# ESP-HI-C3-RevA-schematic.net
KiCad netlist of a schematic drawn in EasyEDA
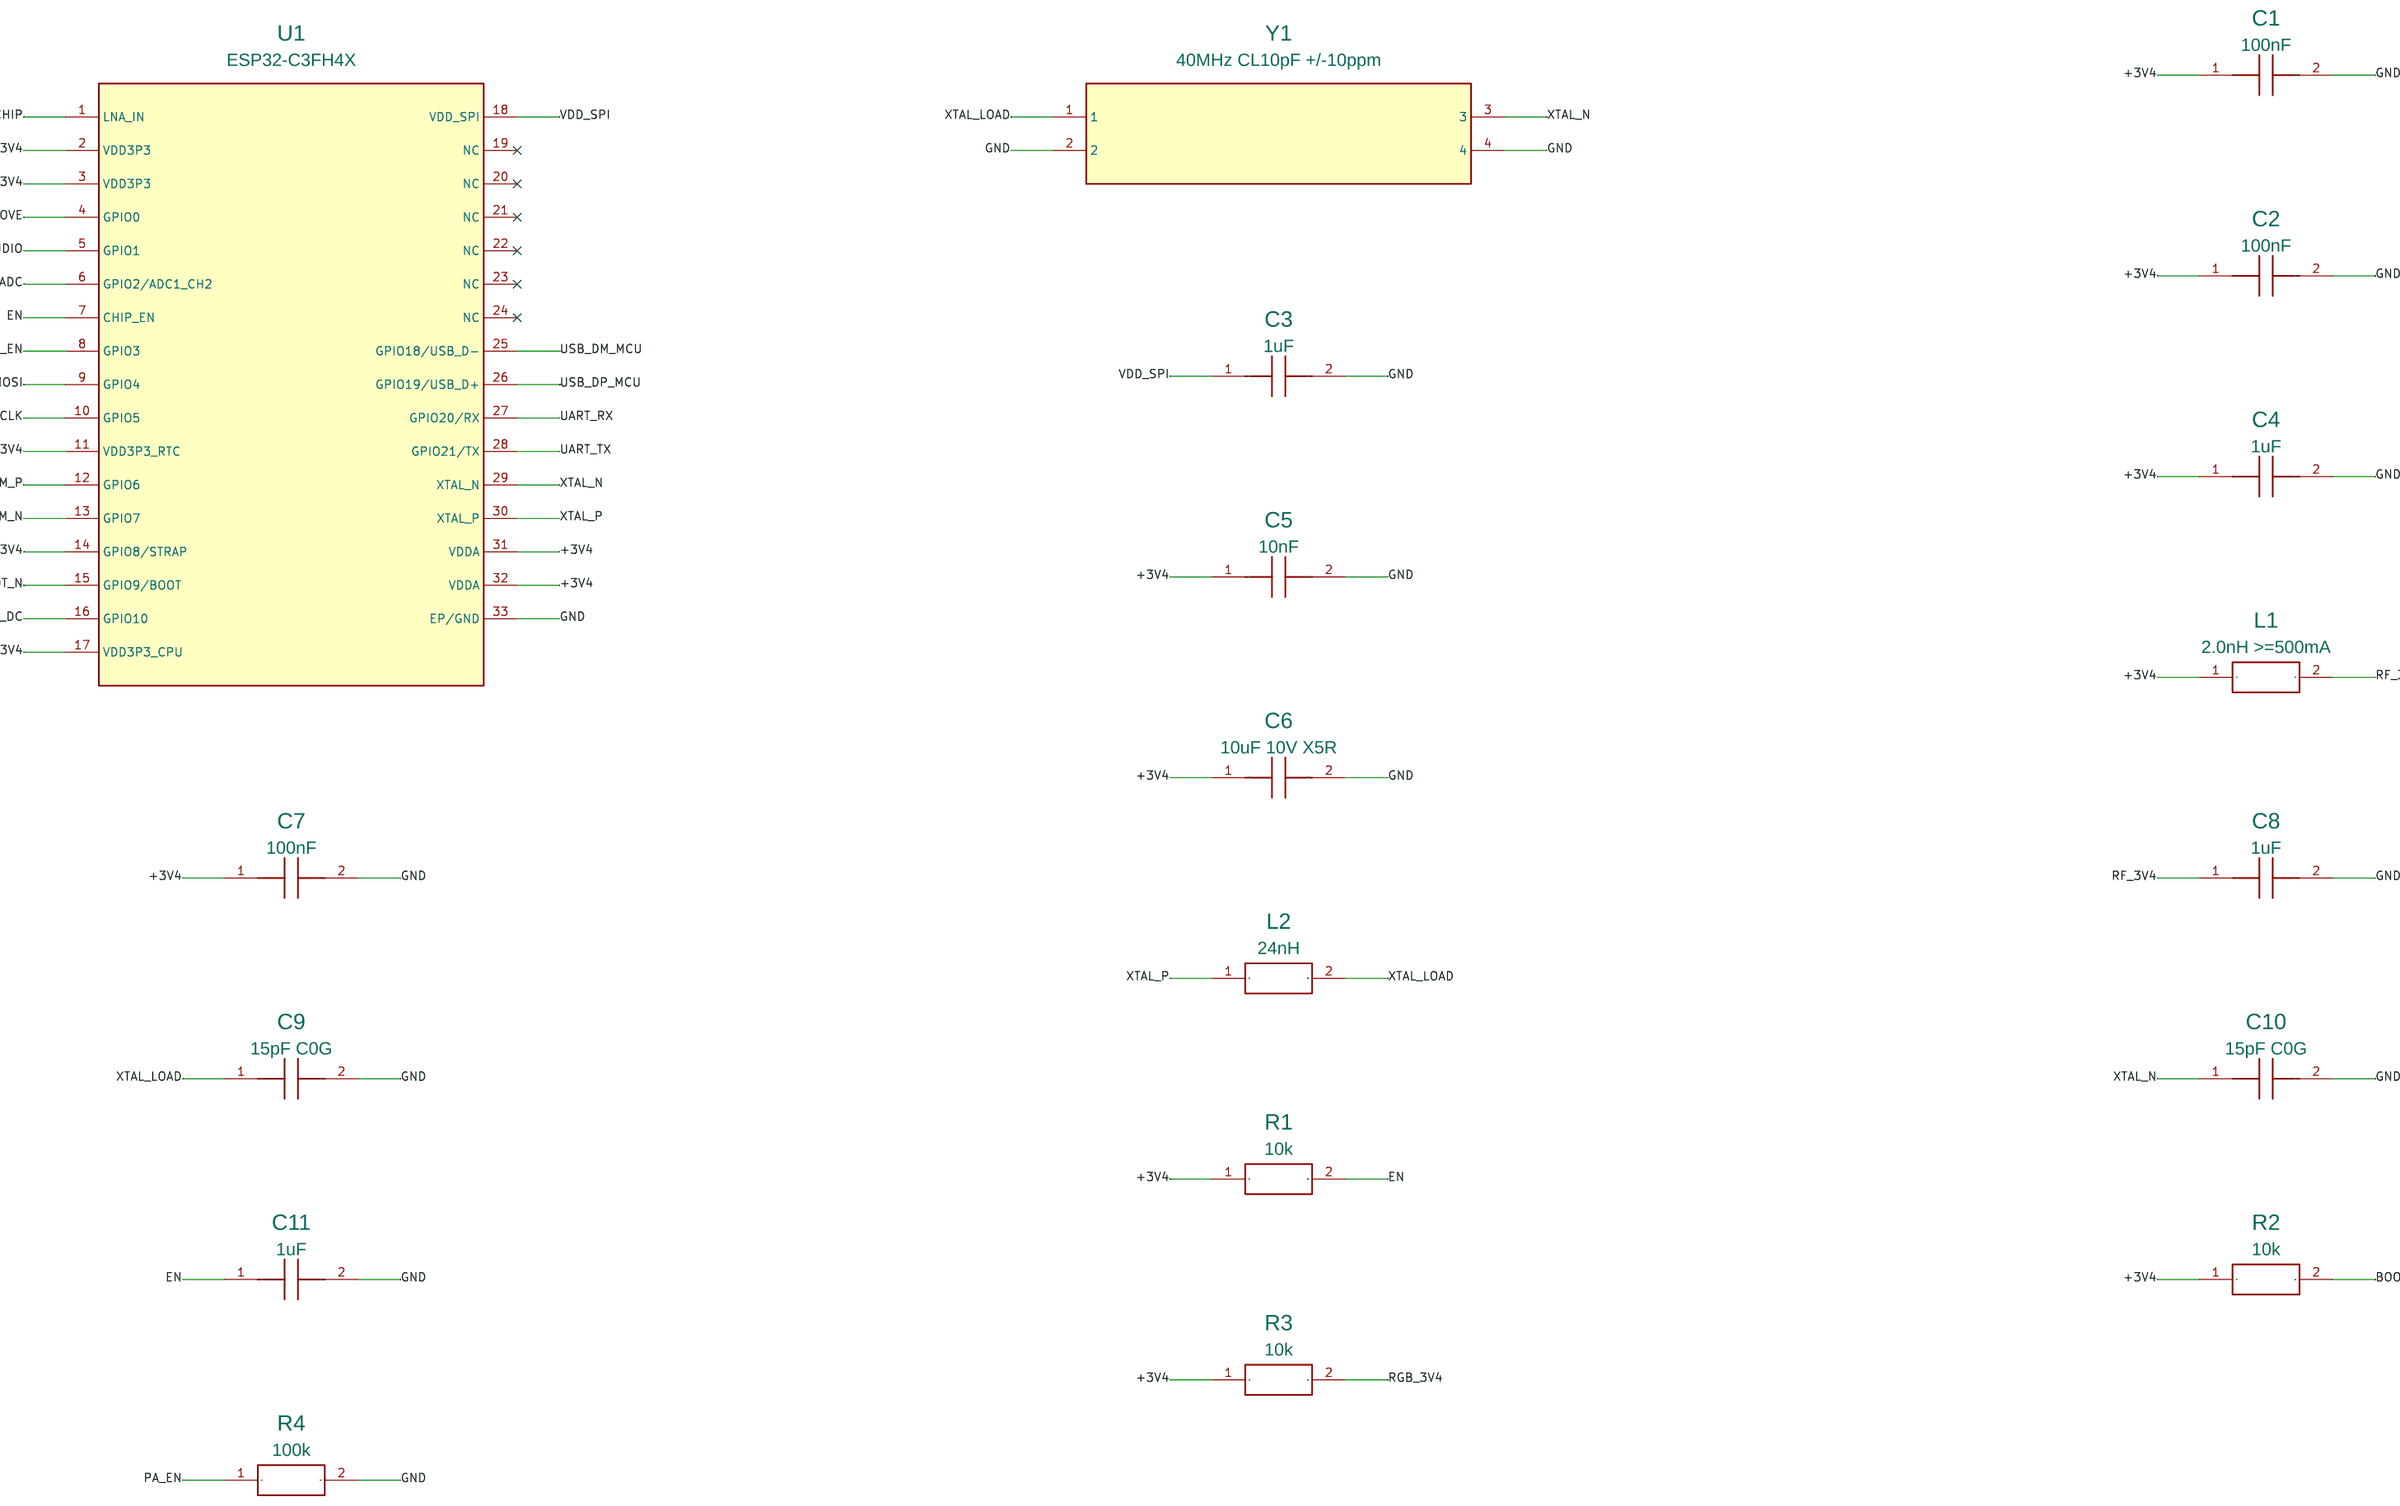
[diagram p0: 01 MCU, crystal and reset]
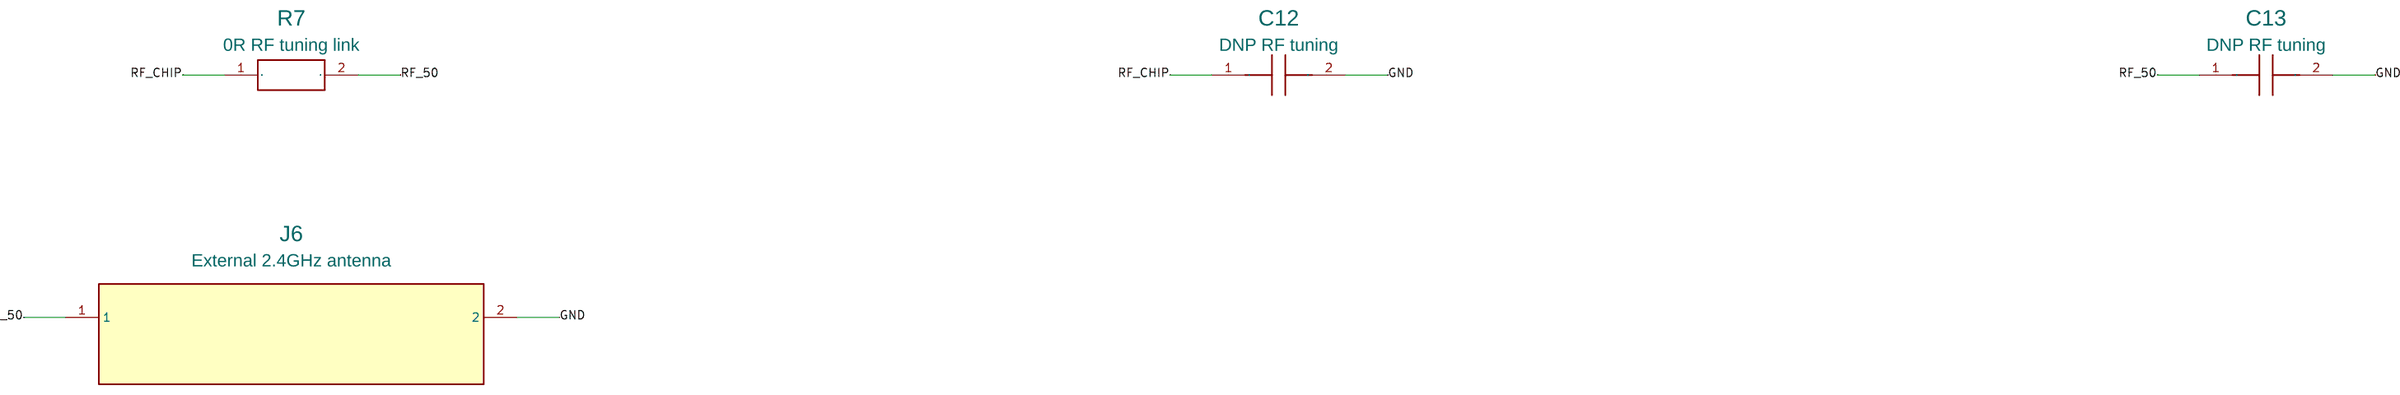
[diagram p1: 02 External antenna and matching]
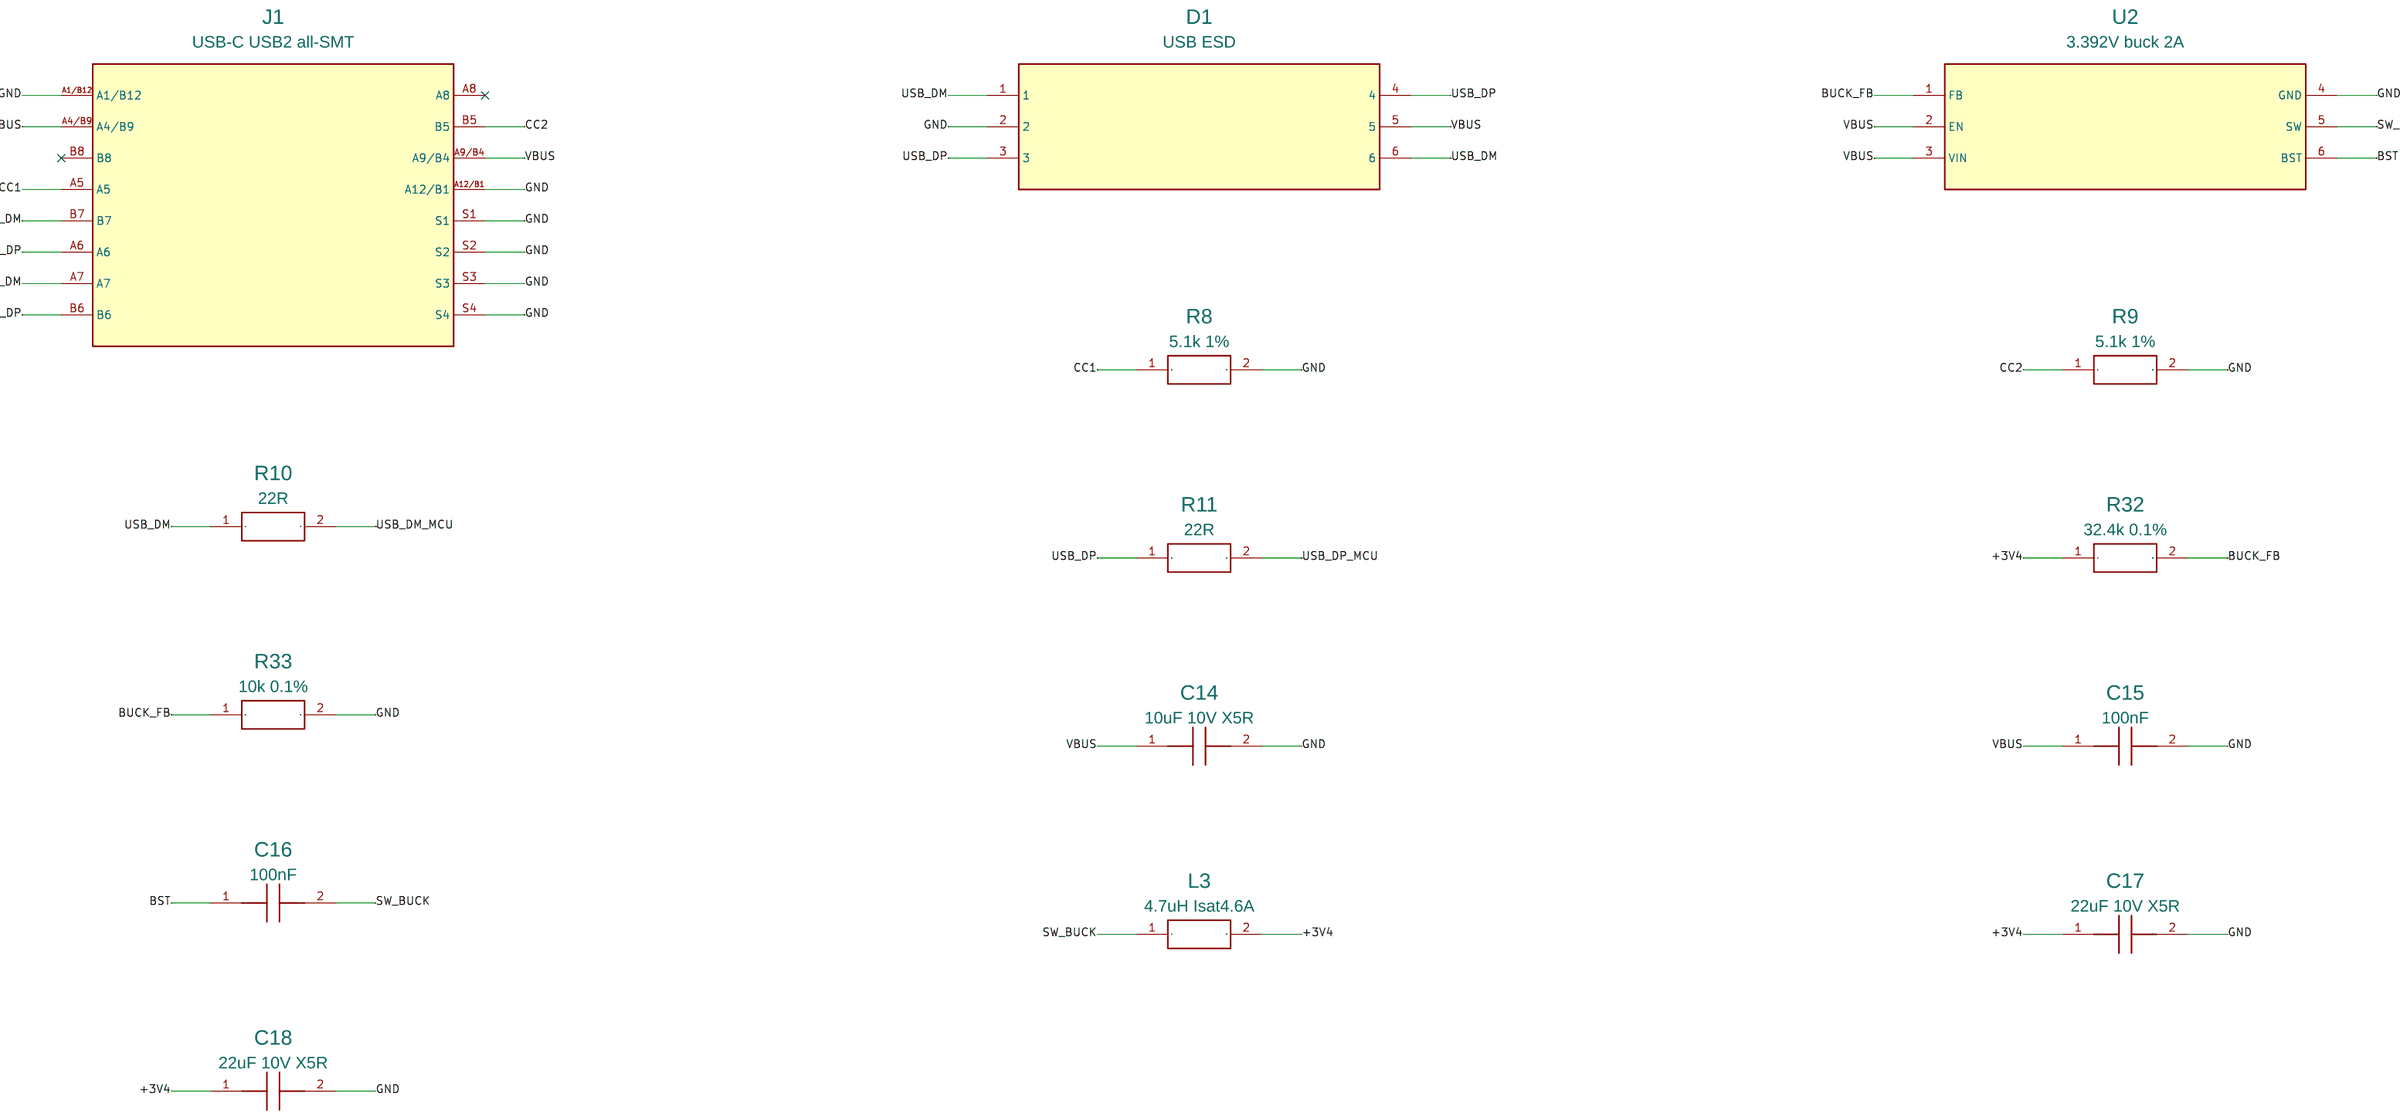
[diagram p2: 03 USB-C and regulated supply]
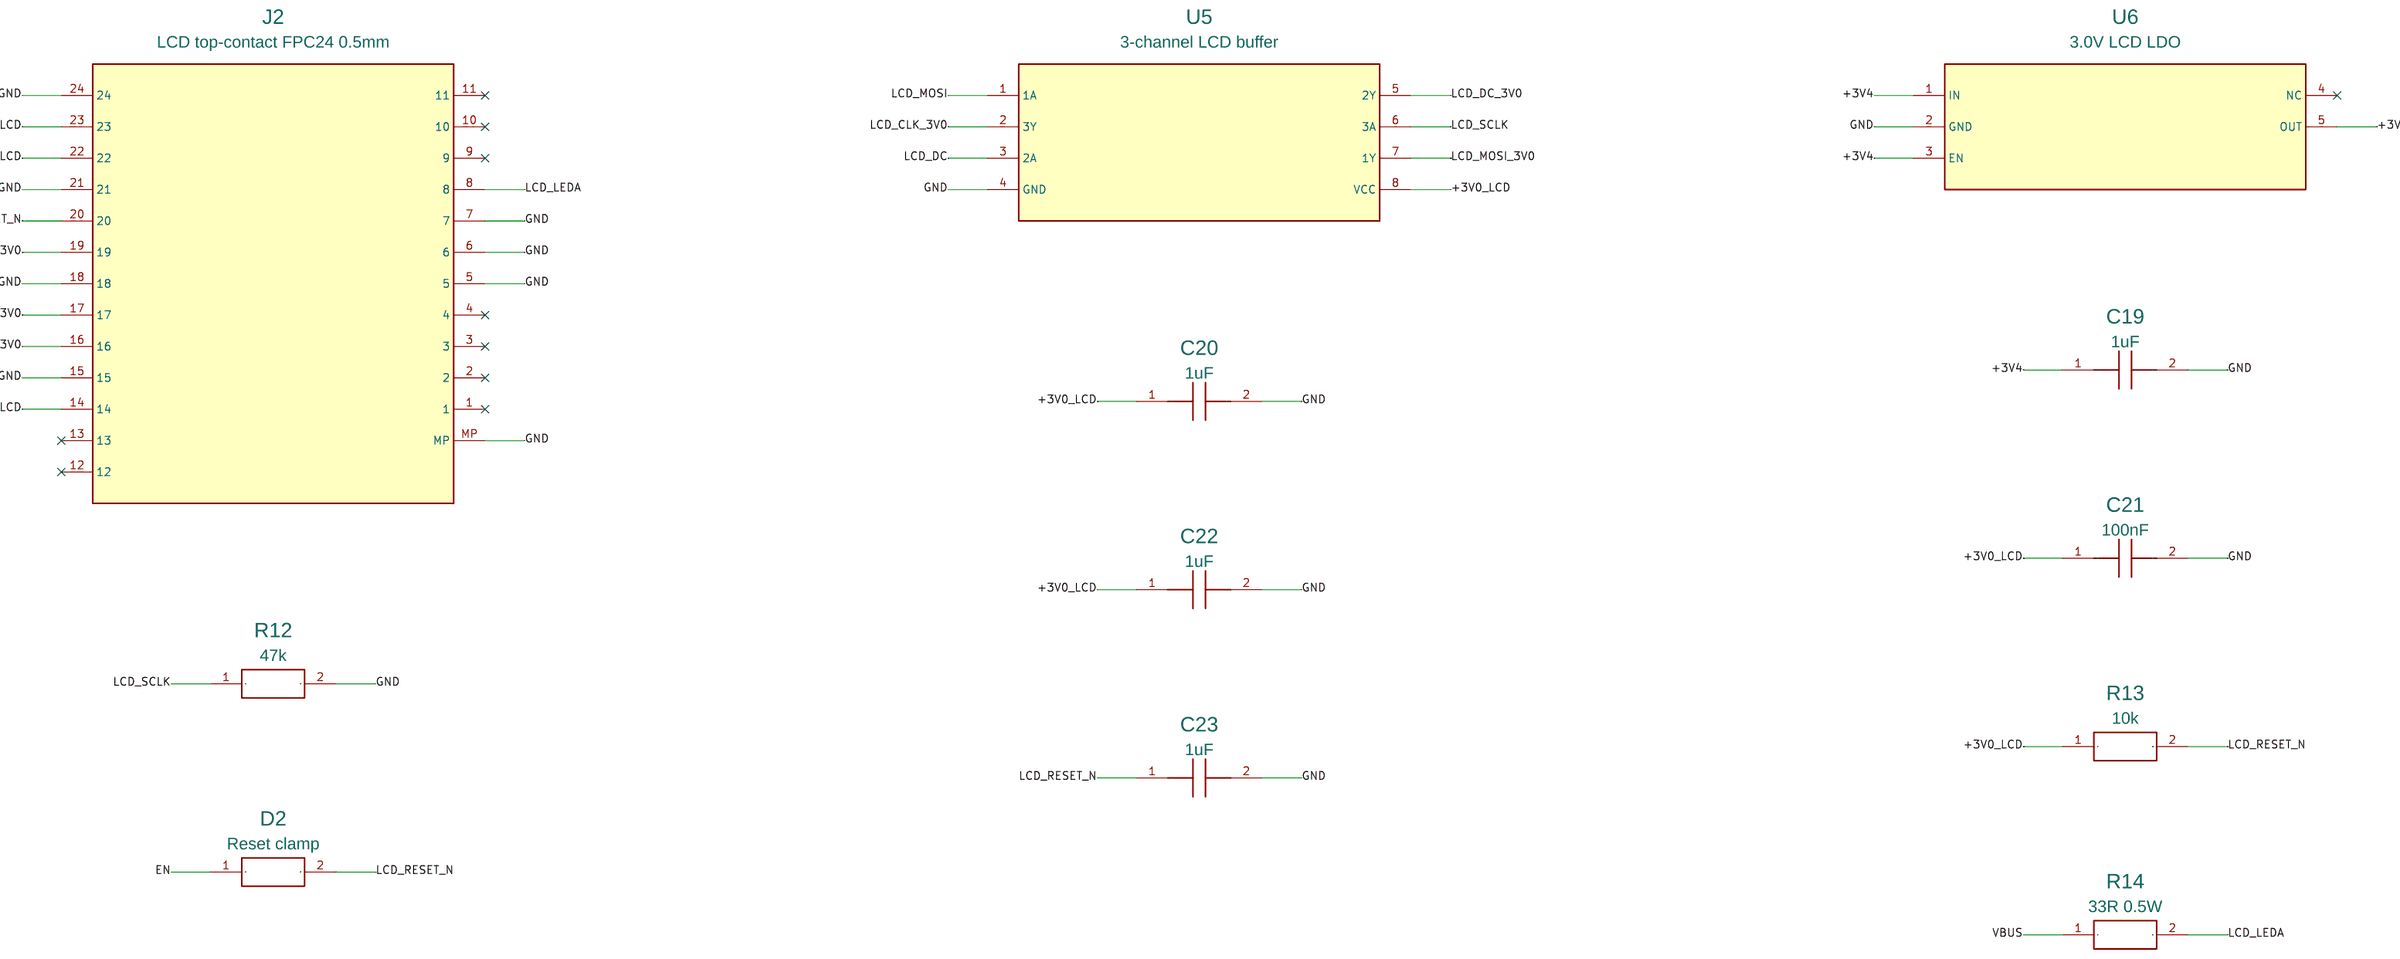
[diagram p3: 04 128x160 SPI display]
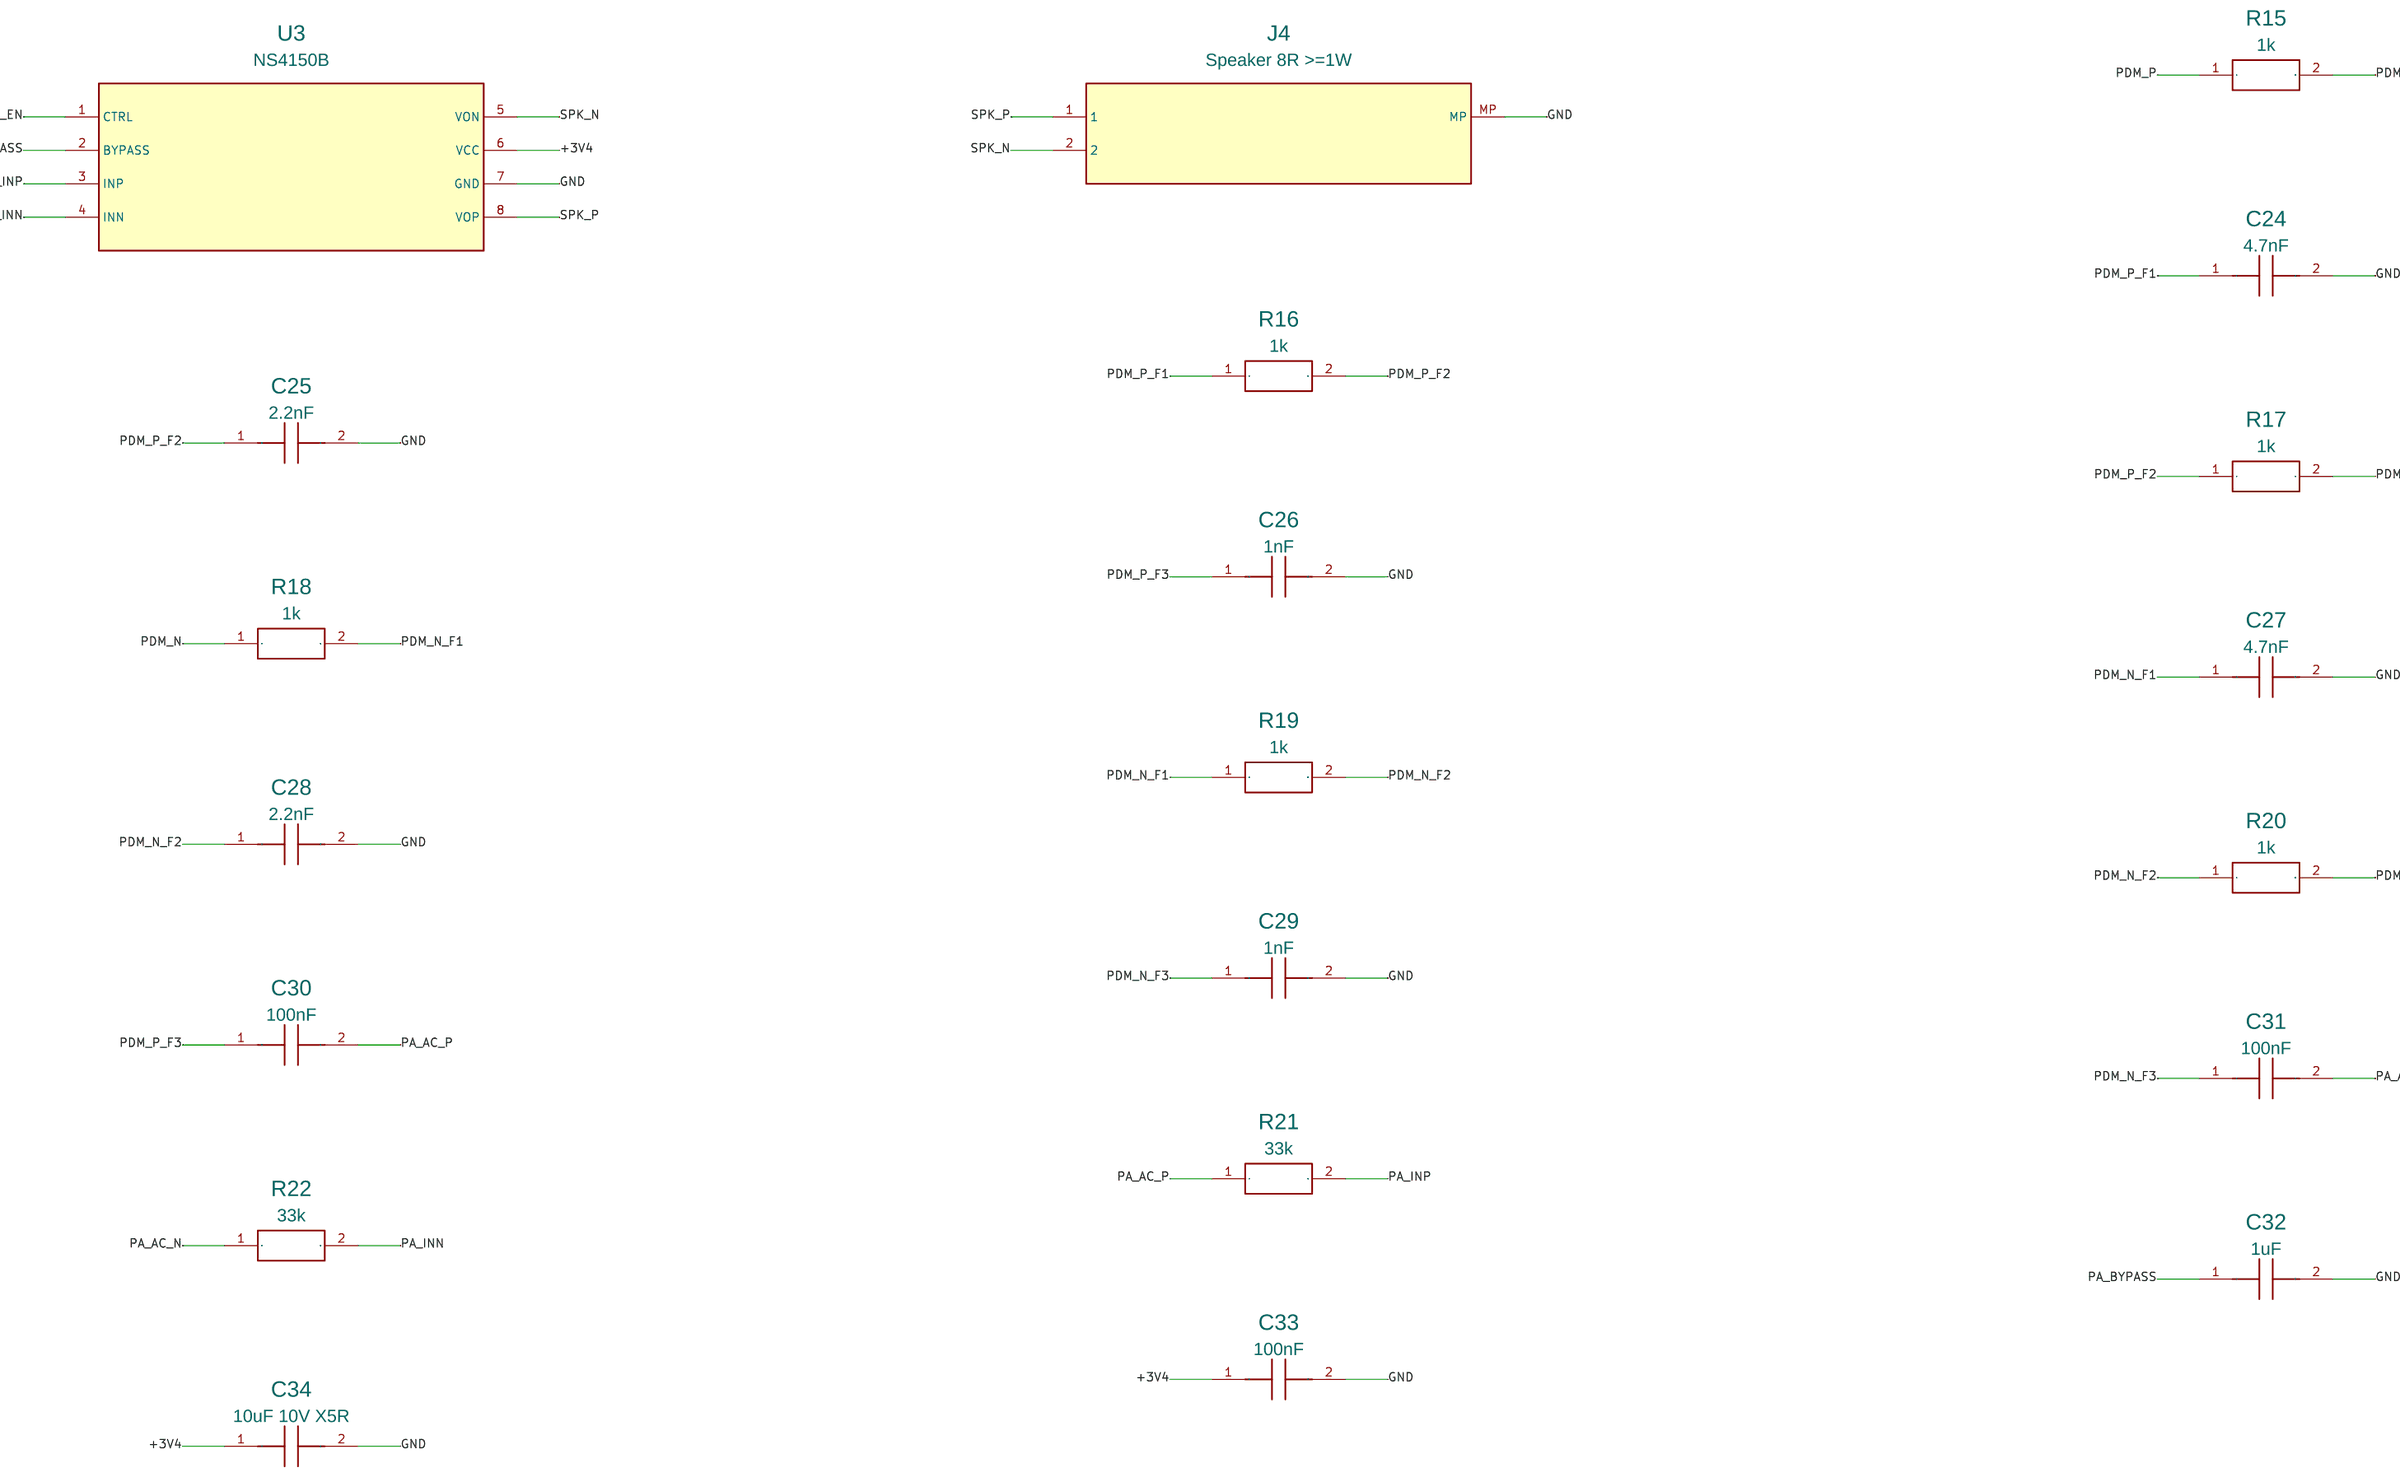
[diagram p4: 05 PDM reconstruction and speaker]
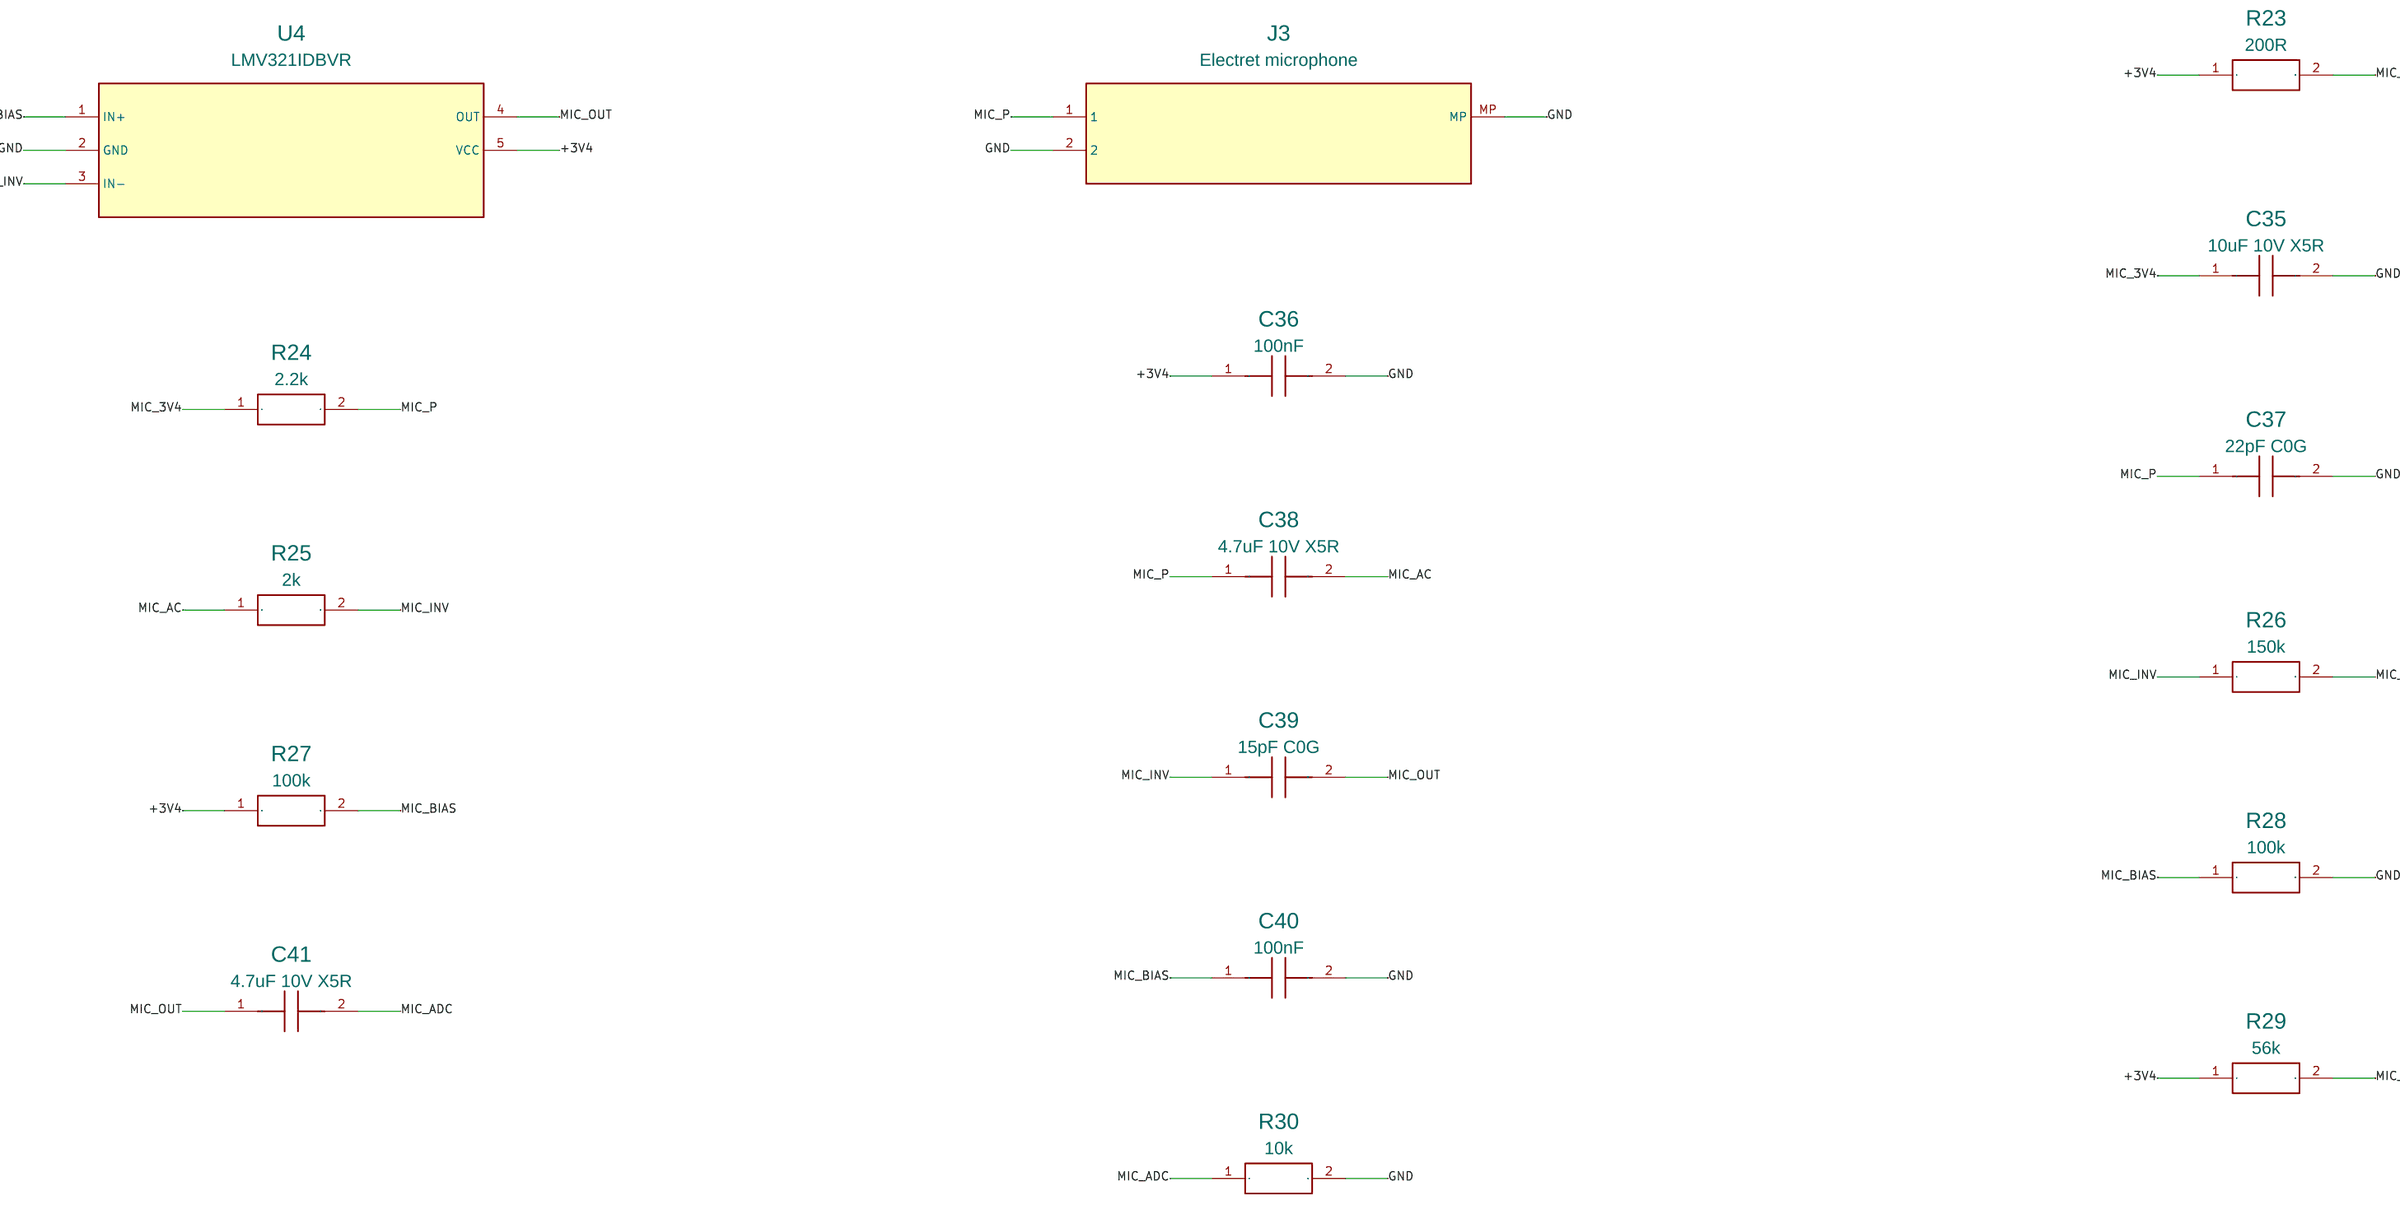
[diagram p5: 06 Electret microphone and ADC]
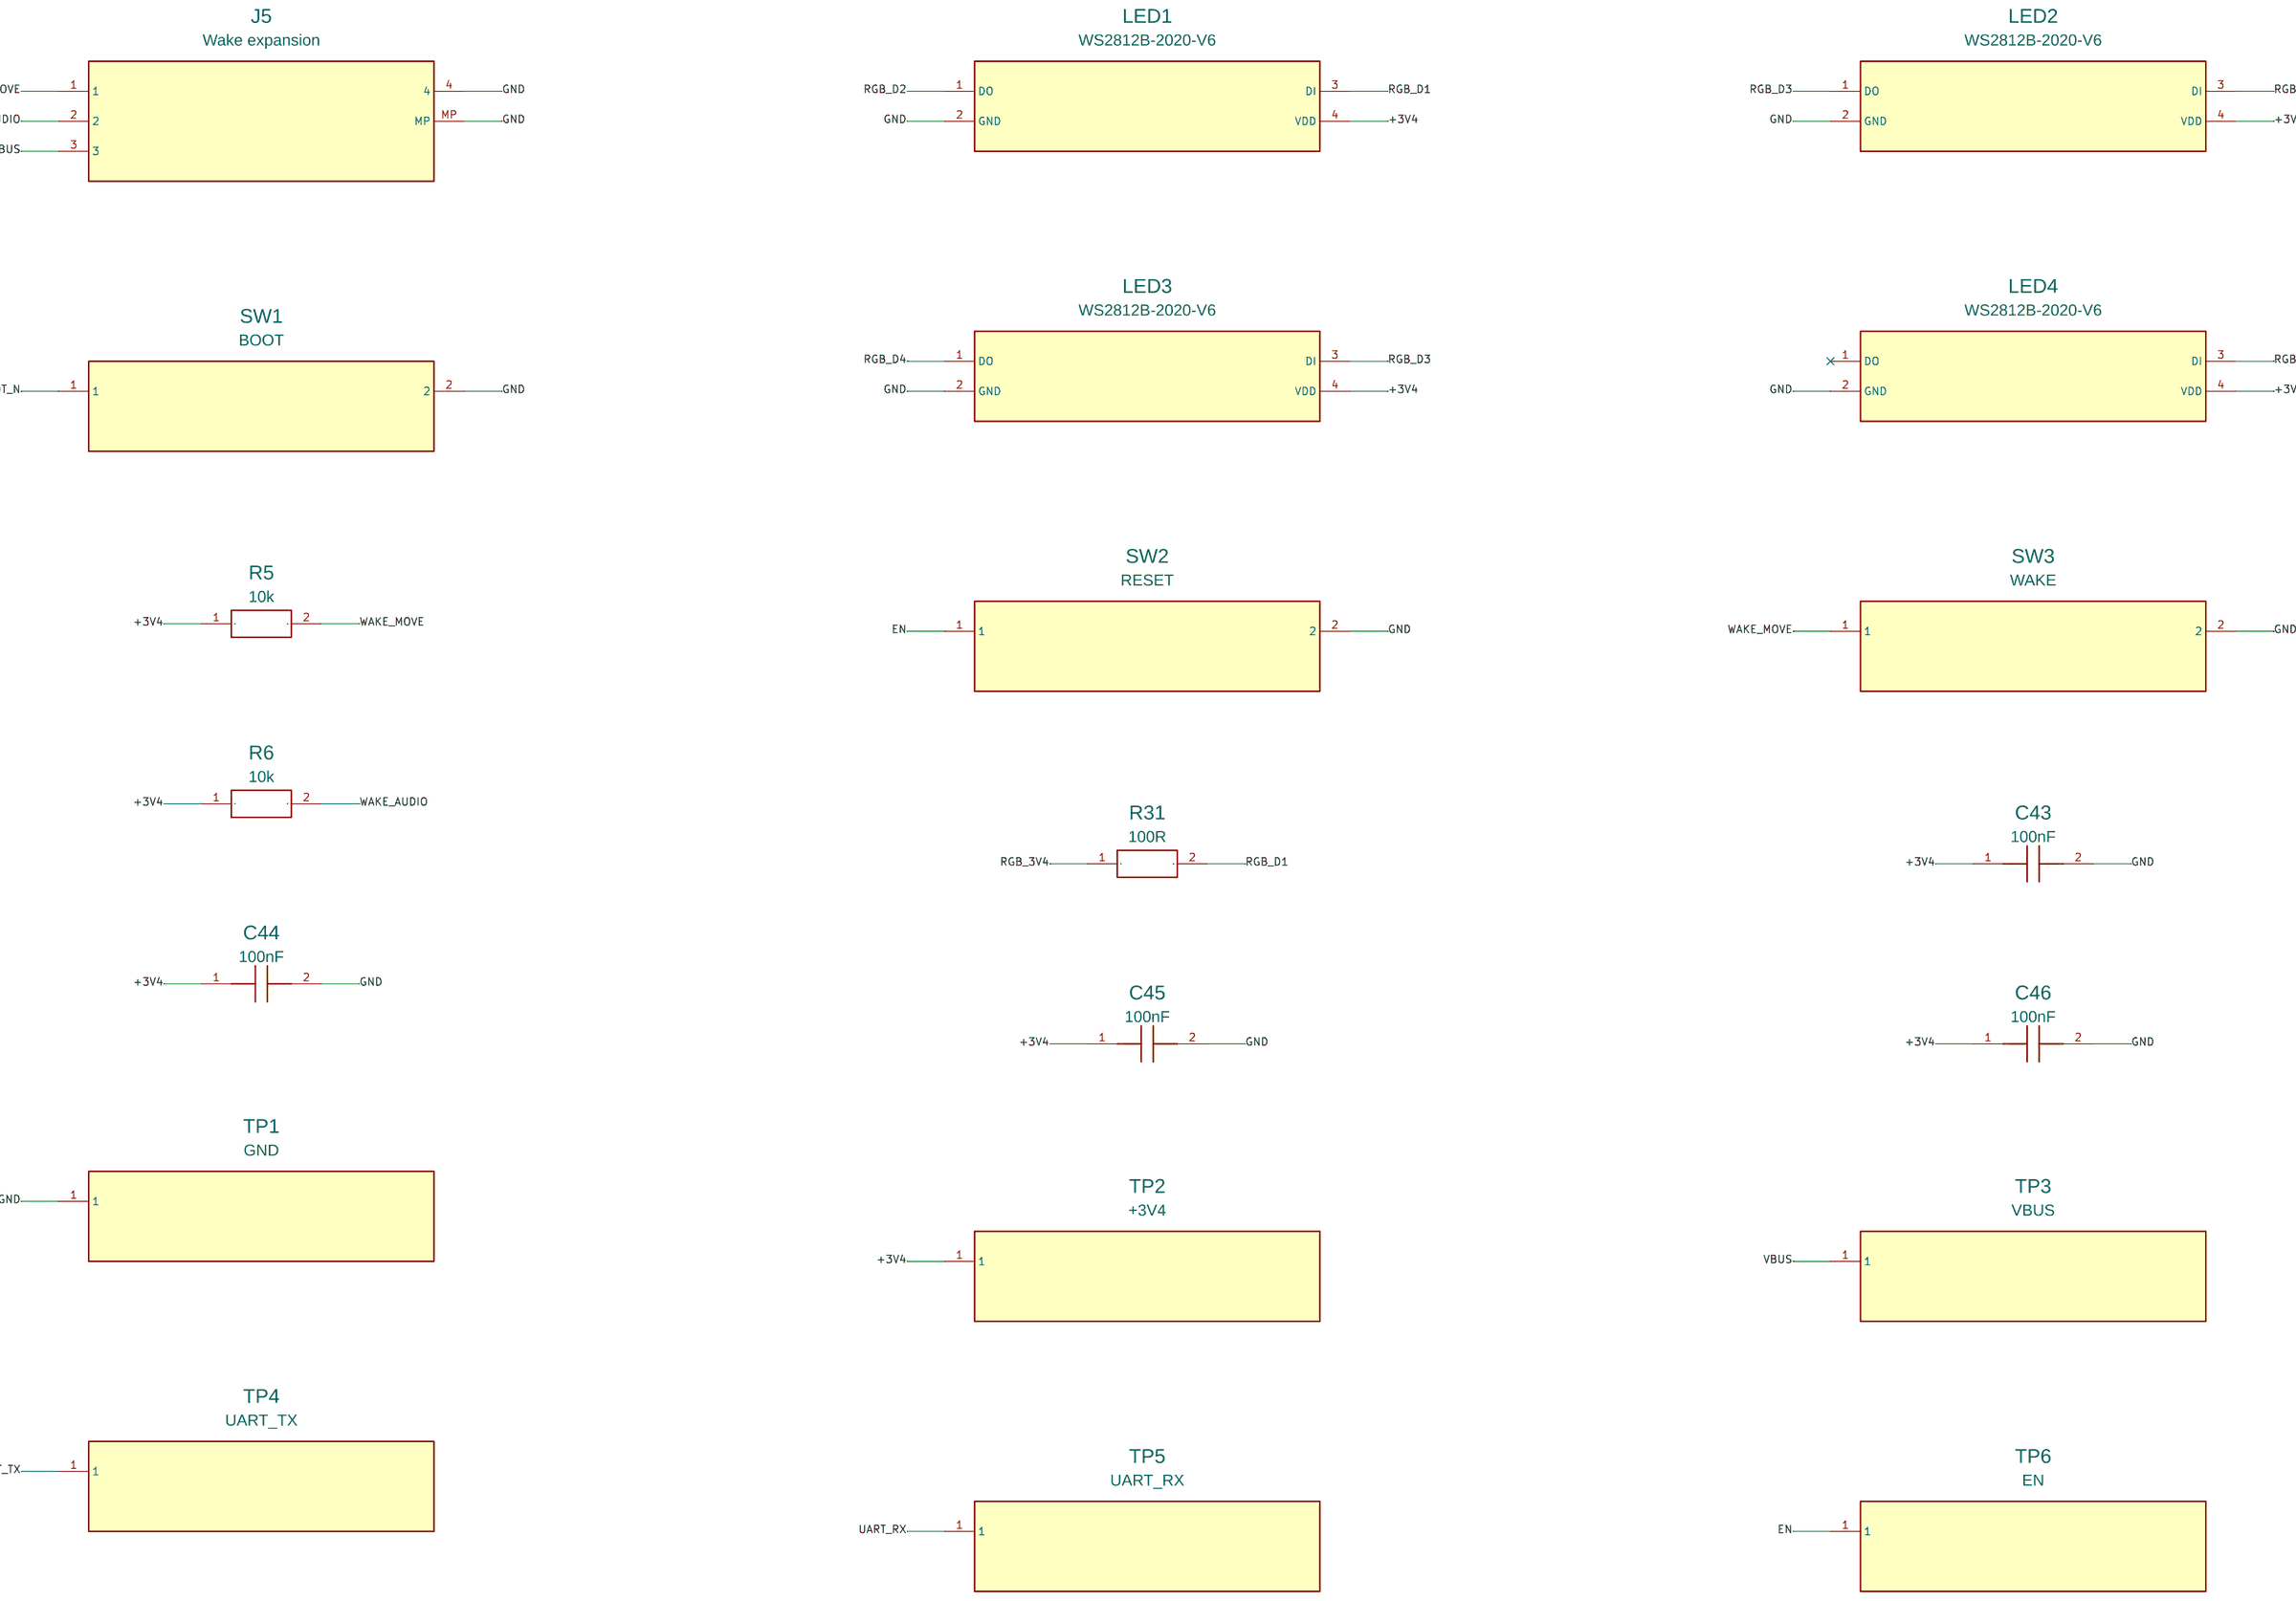
[diagram p6: 07 Buttons, RGB and external IO]

(export (version "E")
  (design (tool "Eeschema 10.0.6"))
  (components
    (comp (ref "C1") (value "100nF") (libsource (lib "") (part "Unknown_1490_145")))
    (comp (ref "C2") (value "100nF") (libsource (lib "") (part "Unknown_1490_265")))
    (comp (ref "C3") (value "1uF") (libsource (lib "") (part "Unknown_900_325")))
    (comp (ref "C4") (value "1uF") (libsource (lib "") (part "Unknown_1490_385")))
    (comp (ref "C5") (value "10nF") (libsource (lib "") (part "Unknown_900_445")))
    (comp (ref "C6") (value "10uF 10V X5R") (libsource (lib "") (part "Unknown_900_565")))
    (comp (ref "C7") (value "100nF") (libsource (lib "") (part "Unknown_310_625")))
    (comp (ref "C8") (value "1uF") (libsource (lib "") (part "Unknown_1490_625")))
    (comp (ref "C9") (value "15pF C0G") (libsource (lib "") (part "Unknown_310_745")))
    (comp (ref "C10") (value "15pF C0G") (libsource (lib "") (part "Unknown_1490_745")))
    (comp (ref "C11") (value "1uF") (libsource (lib "") (part "Unknown_310_865")))
    (comp (ref "L1") (value "2.0nH >=500mA") (libsource (lib "") (part "Unknown_1490_505")))
    (comp (ref "L2") (value "24nH") (libsource (lib "") (part "Unknown_900_685")))
    (comp (ref "R1") (value "10k") (libsource (lib "") (part "Unknown_900_805")))
    (comp (ref "R2") (value "10k") (libsource (lib "") (part "Unknown_1490_865")))
    (comp (ref "R3") (value "10k") (libsource (lib "") (part "Unknown_900_925")))
    (comp (ref "R4") (value "100k") (libsource (lib "") (part "Unknown_310_985")))
    (comp (ref "U1") (value "ESP32-C3FH4X") (libsource (lib "") (part "Unknown_310_330")))
    (comp (ref "Y1")
      (value "40MHz CL10pF +/-10ppm")
      (fields (field (name "Manufacturer Part") "FA-20H 40.0000MF10Z-K3"))
      (libsource (lib "") (part "Unknown_900_180"))
    )
    (comp (ref "C12") (value "DNP RF tuning") (libsource (lib "") (part "Unknown_900_145")))
    (comp (ref "C13") (value "DNP RF tuning") (libsource (lib "") (part "Unknown_1490_145")))
    (comp (ref "J6")
      (value "External 2.4GHz antenna")
      (fields (field (name "Manufacturer Part") "U.FL-R-SMT-1(10)"))
      (libsource (lib "") (part "Unknown_310_300"))
    )
    (comp (ref "R7") (value "0R RF tuning link") (libsource (lib "") (part "Unknown_310_145")))
    (comp (ref "C14") (value "10uF 10V X5R") (libsource (lib "") (part "Unknown_900_585")))
    (comp (ref "C15") (value "100nF") (libsource (lib "") (part "Unknown_1490_585")))
    (comp (ref "C16") (value "100nF") (libsource (lib "") (part "Unknown_310_685")))
    (comp (ref "C17") (value "22uF 10V X5R") (libsource (lib "") (part "Unknown_1490_705")))
    (comp (ref "C18") (value "22uF 10V X5R") (libsource (lib "") (part "Unknown_310_805")))
    (comp (ref "D1")
      (value "USB ESD")
      (fields (field (name "Manufacturer Part") "USBLC6-2SC6"))
      (libsource (lib "") (part "Unknown_900_190"))
    )
    (comp (ref "J1")
      (value "USB-C USB2 all-SMT")
      (fields (field (name "Manufacturer Part") "USB4110-GF-A"))
      (libsource (lib "") (part "Unknown_310_240"))
    )
    (comp (ref "L3")
      (value "4.7uH Isat4.6A")
      (fields (field (name "Manufacturer Part") "XAL4030-472MEC"))
      (libsource (lib "") (part "Unknown_900_705"))
    )
    (comp (ref "R8") (value "5.1k 1%") (libsource (lib "") (part "Unknown_900_345")))
    (comp (ref "R9") (value "5.1k 1%") (libsource (lib "") (part "Unknown_1490_345")))
    (comp (ref "R10") (value "22R") (libsource (lib "") (part "Unknown_310_445")))
    (comp (ref "R11") (value "22R") (libsource (lib "") (part "Unknown_900_465")))
    (comp (ref "R32") (value "32.4k 0.1%") (libsource (lib "") (part "Unknown_1490_465")))
    (comp (ref "R33") (value "10k 0.1%") (libsource (lib "") (part "Unknown_310_565")))
    (comp (ref "U2")
      (value "3.392V buck 2A")
      (fields (field (name "Manufacturer Part") "AP63200WU-7"))
      (libsource (lib "") (part "Unknown_1490_190"))
    )
    (comp (ref "C19") (value "1uF") (libsource (lib "") (part "Unknown_1490_345")))
    (comp (ref "C20") (value "1uF") (libsource (lib "") (part "Unknown_900_365")))
    (comp (ref "C21") (value "100nF") (libsource (lib "") (part "Unknown_1490_465")))
    (comp (ref "C22") (value "1uF") (libsource (lib "") (part "Unknown_900_485")))
    (comp (ref "C23") (value "1uF") (libsource (lib "") (part "Unknown_900_605")))
    (comp (ref "D2")
      (value "Reset clamp")
      (fields (field (name "Manufacturer Part") "BAT54WS"))
      (libsource (lib "") (part "Unknown_310_665"))
    )
    (comp (ref "J2")
      (value "LCD top-contact FPC24 0.5mm")
      (fields (field (name "Manufacturer Part") "52435-2471"))
      (libsource (lib "") (part "Unknown_310_290"))
    )
    (comp (ref "R12") (value "47k") (libsource (lib "") (part "Unknown_310_545")))
    (comp (ref "R13") (value "10k") (libsource (lib "") (part "Unknown_1490_585")))
    (comp (ref "R14") (value "33R 0.5W") (libsource (lib "") (part "Unknown_1490_705")))
    (comp (ref "U5")
      (value "3-channel LCD buffer")
      (fields (field (name "Manufacturer Part") "SN74LVC3G17DCUR"))
      (libsource (lib "") (part "Unknown_900_200"))
    )
    (comp (ref "U6")
      (value "3.0V LCD LDO")
      (fields (field (name "Manufacturer Part") "TLV70030DDCR"))
      (libsource (lib "") (part "Unknown_1490_190"))
    )
    (comp (ref "C24") (value "4.7nF") (libsource (lib "") (part "Unknown_1490_265")))
    (comp (ref "C25") (value "2.2nF") (libsource (lib "") (part "Unknown_310_365")))
    (comp (ref "C26") (value "1nF") (libsource (lib "") (part "Unknown_900_445")))
    (comp (ref "C27") (value "4.7nF") (libsource (lib "") (part "Unknown_1490_505")))
    (comp (ref "C28") (value "2.2nF") (libsource (lib "") (part "Unknown_310_605")))
    (comp (ref "C29") (value "1nF") (libsource (lib "") (part "Unknown_900_685")))
    (comp (ref "C30") (value "100nF") (libsource (lib "") (part "Unknown_310_725")))
    (comp (ref "C31") (value "100nF") (libsource (lib "") (part "Unknown_1490_745")))
    (comp (ref "C32") (value "1uF") (libsource (lib "") (part "Unknown_1490_865")))
    (comp (ref "C33") (value "100nF") (libsource (lib "") (part "Unknown_900_925")))
    (comp (ref "C34") (value "10uF 10V X5R") (libsource (lib "") (part "Unknown_310_965")))
    (comp (ref "J4")
      (value "Speaker 8R >=1W")
      (fields (field (name "Manufacturer Part") "SM02B-SRSS-TB(LF)(SN)"))
      (libsource (lib "") (part "Unknown_900_180"))
    )
    (comp (ref "R15") (value "1k") (libsource (lib "") (part "Unknown_1490_145")))
    (comp (ref "R16") (value "1k") (libsource (lib "") (part "Unknown_900_325")))
    (comp (ref "R17") (value "1k") (libsource (lib "") (part "Unknown_1490_385")))
    (comp (ref "R18") (value "1k") (libsource (lib "") (part "Unknown_310_485")))
    (comp (ref "R19") (value "1k") (libsource (lib "") (part "Unknown_900_565")))
    (comp (ref "R20") (value "1k") (libsource (lib "") (part "Unknown_1490_625")))
    (comp (ref "R21") (value "33k") (libsource (lib "") (part "Unknown_900_805")))
    (comp (ref "R22") (value "33k") (libsource (lib "") (part "Unknown_310_845")))
    (comp (ref "U3") (value "NS4150B") (libsource (lib "") (part "Unknown_310_200")))
    (comp (ref "C35") (value "10uF 10V X5R") (libsource (lib "") (part "Unknown_1490_265")))
    (comp (ref "C36") (value "100nF") (libsource (lib "") (part "Unknown_900_325")))
    (comp (ref "C37") (value "22pF C0G") (libsource (lib "") (part "Unknown_1490_385")))
    (comp (ref "C38") (value "4.7uF 10V X5R") (libsource (lib "") (part "Unknown_900_445")))
    (comp (ref "C39") (value "15pF C0G") (libsource (lib "") (part "Unknown_900_565")))
    (comp (ref "C40") (value "100nF") (libsource (lib "") (part "Unknown_900_685")))
    (comp (ref "C41") (value "4.7uF 10V X5R") (libsource (lib "") (part "Unknown_310_705")))
    (comp (ref "J3")
      (value "Electret microphone")
      (fields (field (name "Manufacturer Part") "SM02B-SRSS-TB(LF)(SN)"))
      (libsource (lib "") (part "Unknown_900_180"))
    )
    (comp (ref "R23") (value "200R") (libsource (lib "") (part "Unknown_1490_145")))
    (comp (ref "R24") (value "2.2k") (libsource (lib "") (part "Unknown_310_345")))
    (comp (ref "R25") (value "2k") (libsource (lib "") (part "Unknown_310_465")))
    (comp (ref "R26") (value "150k") (libsource (lib "") (part "Unknown_1490_505")))
    (comp (ref "R27") (value "100k") (libsource (lib "") (part "Unknown_310_585")))
    (comp (ref "R28") (value "100k") (libsource (lib "") (part "Unknown_1490_625")))
    (comp (ref "R29") (value "56k") (libsource (lib "") (part "Unknown_1490_745")))
    (comp (ref "R30") (value "10k") (libsource (lib "") (part "Unknown_900_805")))
    (comp (ref "U4") (value "LMV321IDBVR") (libsource (lib "") (part "Unknown_310_190")))
    (comp (ref "C43") (value "100nF") (libsource (lib "") (part "Unknown_1490_685")))
    (comp (ref "C44") (value "100nF") (libsource (lib "") (part "Unknown_310_765")))
    (comp (ref "C45") (value "100nF") (libsource (lib "") (part "Unknown_900_805")))
    (comp (ref "C46") (value "100nF") (libsource (lib "") (part "Unknown_1490_805")))
    (comp (ref "J5")
      (value "Wake expansion")
      (fields (field (name "Manufacturer Part") "SM04B-SRSS-TB(LF)(SN)"))
      (libsource (lib "") (part "Unknown_310_190"))
    )
    (comp (ref "LED1") (value "WS2812B-2020-V6") (libsource (lib "") (part "Unknown_900_180")))
    (comp (ref "LED2") (value "WS2812B-2020-V6") (libsource (lib "") (part "Unknown_1490_180")))
    (comp (ref "LED3") (value "WS2812B-2020-V6") (libsource (lib "") (part "Unknown_900_360")))
    (comp (ref "LED4") (value "WS2812B-2020-V6") (libsource (lib "") (part "Unknown_1490_360")))
    (comp (ref "R5") (value "10k") (libsource (lib "") (part "Unknown_310_525")))
    (comp (ref "R6") (value "10k") (libsource (lib "") (part "Unknown_310_645")))
    (comp (ref "R31") (value "100R") (libsource (lib "") (part "Unknown_900_685")))
    (comp (ref "SW1")
      (value "BOOT")
      (fields (field (name "Manufacturer Part") "PTS810 SJM 250 SMTR LFS"))
      (libsource (lib "") (part "Unknown_310_380"))
    )
    (comp (ref "SW2")
      (value "RESET")
      (fields (field (name "Manufacturer Part") "PTS810 SJM 250 SMTR LFS"))
      (libsource (lib "") (part "Unknown_900_540"))
    )
    (comp (ref "SW3")
      (value "WAKE")
      (fields (field (name "Manufacturer Part") "PTS810 SJM 250 SMTR LFS"))
      (libsource (lib "") (part "Unknown_1490_540"))
    )
    (comp (ref "TP1") (value "GND") (libsource (lib "") (part "Unknown_310_920")))
    (comp (ref "TP2") (value "+3V4") (libsource (lib "") (part "Unknown_900_960")))
    (comp (ref "TP3") (value "VBUS") (libsource (lib "") (part "Unknown_1490_960")))
    (comp (ref "TP4") (value "UART_TX") (libsource (lib "") (part "Unknown_310_1100")))
    (comp (ref "TP5") (value "UART_RX") (libsource (lib "") (part "Unknown_900_1140")))
    (comp (ref "TP6") (value "EN") (libsource (lib "") (part "Unknown_1490_1140")))
  )
  (nets
    (net (code "1") (name "+3V0_LCD") (class "Default")
      (node (ref "C20") (pin "1") (pinfunction "1_1") (pintype "unspecified"))
      (node (ref "C21") (pin "1") (pinfunction "1_1") (pintype "unspecified"))
      (node (ref "C22") (pin "1") (pinfunction "1_1") (pintype "unspecified"))
      (node (ref "J2") (pin "14") (pinfunction "14_14") (pintype "unspecified"))
      (node (ref "J2") (pin "22") (pinfunction "22_22") (pintype "unspecified"))
      (node (ref "J2") (pin "23") (pinfunction "23_23") (pintype "unspecified"))
      (node (ref "R13") (pin "1") (pinfunction "1_1") (pintype "unspecified"))
      (node (ref "U5") (pin "8") (pinfunction "VCC_8") (pintype "unspecified"))
      (node (ref "U6") (pin "5") (pinfunction "OUT_5") (pintype "unspecified"))
    )
    (net (code "2") (name "+3V4") (class "Default")
      (node (ref "C1") (pin "1") (pinfunction "1_1") (pintype "unspecified"))
      (node (ref "C17") (pin "1") (pinfunction "1_1") (pintype "unspecified"))
      (node (ref "C18") (pin "1") (pinfunction "1_1") (pintype "unspecified"))
      (node (ref "C19") (pin "1") (pinfunction "1_1") (pintype "unspecified"))
      (node (ref "C2") (pin "1") (pinfunction "1_1") (pintype "unspecified"))
      (node (ref "C33") (pin "1") (pinfunction "1_1") (pintype "unspecified"))
      (node (ref "C34") (pin "1") (pinfunction "1_1") (pintype "unspecified"))
      (node (ref "C36") (pin "1") (pinfunction "1_1") (pintype "unspecified"))
      (node (ref "C4") (pin "1") (pinfunction "1_1") (pintype "unspecified"))
      (node (ref "C43") (pin "1") (pinfunction "1_1") (pintype "unspecified"))
      (node (ref "C44") (pin "1") (pinfunction "1_1") (pintype "unspecified"))
      (node (ref "C45") (pin "1") (pinfunction "1_1") (pintype "unspecified"))
      (node (ref "C46") (pin "1") (pinfunction "1_1") (pintype "unspecified"))
      (node (ref "C5") (pin "1") (pinfunction "1_1") (pintype "unspecified"))
      (node (ref "C6") (pin "1") (pinfunction "1_1") (pintype "unspecified"))
      (node (ref "C7") (pin "1") (pinfunction "1_1") (pintype "unspecified"))
      (node (ref "L1") (pin "1") (pinfunction "1_1") (pintype "unspecified"))
      (node (ref "L3") (pin "2") (pinfunction "2_2") (pintype "unspecified"))
      (node (ref "LED1") (pin "4") (pinfunction "VDD_4") (pintype "unspecified"))
      (node (ref "LED2") (pin "4") (pinfunction "VDD_4") (pintype "unspecified"))
      (node (ref "LED3") (pin "4") (pinfunction "VDD_4") (pintype "unspecified"))
      (node (ref "LED4") (pin "4") (pinfunction "VDD_4") (pintype "unspecified"))
      (node (ref "R1") (pin "1") (pinfunction "1_1") (pintype "unspecified"))
      (node (ref "R2") (pin "1") (pinfunction "1_1") (pintype "unspecified"))
      (node (ref "R23") (pin "1") (pinfunction "1_1") (pintype "unspecified"))
      (node (ref "R27") (pin "1") (pinfunction "1_1") (pintype "unspecified"))
      (node (ref "R29") (pin "1") (pinfunction "1_1") (pintype "unspecified"))
      (node (ref "R3") (pin "1") (pinfunction "1_1") (pintype "unspecified"))
      (node (ref "R32") (pin "1") (pinfunction "1_1") (pintype "unspecified"))
      (node (ref "R5") (pin "1") (pinfunction "1_1") (pintype "unspecified"))
      (node (ref "R6") (pin "1") (pinfunction "1_1") (pintype "unspecified"))
      (node (ref "TP2") (pin "1") (pinfunction "1_1") (pintype "unspecified"))
      (node (ref "U1") (pin "11") (pinfunction "VDD3P3_RTC_11") (pintype "unspecified"))
      (node (ref "U1") (pin "17") (pinfunction "VDD3P3_CPU_17") (pintype "unspecified"))
      (node (ref "U1") (pin "31") (pinfunction "VDDA_31") (pintype "unspecified"))
      (node (ref "U1") (pin "32") (pinfunction "VDDA_32") (pintype "unspecified"))
      (node (ref "U3") (pin "6") (pinfunction "VCC_6") (pintype "unspecified"))
      (node (ref "U4") (pin "5") (pinfunction "VCC_5") (pintype "unspecified"))
      (node (ref "U6") (pin "1") (pinfunction "IN_1") (pintype "unspecified"))
      (node (ref "U6") (pin "3") (pinfunction "EN_3") (pintype "unspecified"))
    )
    (net (code "3") (name "BOOT_N") (class "Default")
      (node (ref "R2") (pin "2") (pinfunction "2_2") (pintype "unspecified"))
      (node (ref "SW1") (pin "1") (pinfunction "1_1") (pintype "unspecified"))
      (node (ref "U1") (pin "15") (pinfunction "GPIO9/BOOT_15") (pintype "unspecified"))
    )
    (net (code "4") (name "BST") (class "Default")
      (node (ref "C16") (pin "1") (pinfunction "1_1") (pintype "unspecified"))
      (node (ref "U2") (pin "6") (pinfunction "BST_6") (pintype "unspecified"))
    )
    (net (code "5") (name "BUCK_FB") (class "Default")
      (node (ref "R32") (pin "2") (pinfunction "2_2") (pintype "unspecified"))
      (node (ref "R33") (pin "1") (pinfunction "1_1") (pintype "unspecified"))
      (node (ref "U2") (pin "1") (pinfunction "FB_1") (pintype "unspecified"))
    )
    (net (code "6") (name "CC1") (class "Default")
      (node (ref "J1") (pin "A5") (pinfunction "A5_A5") (pintype "unspecified"))
      (node (ref "R8") (pin "1") (pinfunction "1_1") (pintype "unspecified"))
    )
    (net (code "7") (name "CC2") (class "Default")
      (node (ref "J1") (pin "B5") (pinfunction "B5_B5") (pintype "unspecified"))
      (node (ref "R9") (pin "1") (pinfunction "1_1") (pintype "unspecified"))
    )
    (net (code "8") (name "EN") (class "Default")
      (node (ref "C11") (pin "1") (pinfunction "1_1") (pintype "unspecified"))
      (node (ref "D2") (pin "1") (pinfunction "1_1") (pintype "unspecified"))
      (node (ref "R1") (pin "2") (pinfunction "2_2") (pintype "unspecified"))
      (node (ref "SW2") (pin "1") (pinfunction "1_1") (pintype "unspecified"))
      (node (ref "TP6") (pin "1") (pinfunction "1_1") (pintype "unspecified"))
      (node (ref "U1") (pin "7") (pinfunction "CHIP_EN_7") (pintype "unspecified"))
    )
    (net (code "9") (name "GND") (class "Default")
      (node (ref "C1") (pin "2") (pinfunction "2_2") (pintype "unspecified"))
      (node (ref "C10") (pin "2") (pinfunction "2_2") (pintype "unspecified"))
      (node (ref "C11") (pin "2") (pinfunction "2_2") (pintype "unspecified"))
      (node (ref "C12") (pin "2") (pinfunction "2_2") (pintype "unspecified"))
      (node (ref "C13") (pin "2") (pinfunction "2_2") (pintype "unspecified"))
      (node (ref "C14") (pin "2") (pinfunction "2_2") (pintype "unspecified"))
      (node (ref "C15") (pin "2") (pinfunction "2_2") (pintype "unspecified"))
      (node (ref "C17") (pin "2") (pinfunction "2_2") (pintype "unspecified"))
      (node (ref "C18") (pin "2") (pinfunction "2_2") (pintype "unspecified"))
      (node (ref "C19") (pin "2") (pinfunction "2_2") (pintype "unspecified"))
      (node (ref "C2") (pin "2") (pinfunction "2_2") (pintype "unspecified"))
      (node (ref "C20") (pin "2") (pinfunction "2_2") (pintype "unspecified"))
      (node (ref "C21") (pin "2") (pinfunction "2_2") (pintype "unspecified"))
      (node (ref "C22") (pin "2") (pinfunction "2_2") (pintype "unspecified"))
      (node (ref "C23") (pin "2") (pinfunction "2_2") (pintype "unspecified"))
      (node (ref "C24") (pin "2") (pinfunction "2_2") (pintype "unspecified"))
      (node (ref "C25") (pin "2") (pinfunction "2_2") (pintype "unspecified"))
      (node (ref "C26") (pin "2") (pinfunction "2_2") (pintype "unspecified"))
      (node (ref "C27") (pin "2") (pinfunction "2_2") (pintype "unspecified"))
      (node (ref "C28") (pin "2") (pinfunction "2_2") (pintype "unspecified"))
      (node (ref "C29") (pin "2") (pinfunction "2_2") (pintype "unspecified"))
      (node (ref "C3") (pin "2") (pinfunction "2_2") (pintype "unspecified"))
      (node (ref "C32") (pin "2") (pinfunction "2_2") (pintype "unspecified"))
      (node (ref "C33") (pin "2") (pinfunction "2_2") (pintype "unspecified"))
      (node (ref "C34") (pin "2") (pinfunction "2_2") (pintype "unspecified"))
      (node (ref "C35") (pin "2") (pinfunction "2_2") (pintype "unspecified"))
      (node (ref "C36") (pin "2") (pinfunction "2_2") (pintype "unspecified"))
      (node (ref "C37") (pin "2") (pinfunction "2_2") (pintype "unspecified"))
      (node (ref "C4") (pin "2") (pinfunction "2_2") (pintype "unspecified"))
      (node (ref "C40") (pin "2") (pinfunction "2_2") (pintype "unspecified"))
      (node (ref "C43") (pin "2") (pinfunction "2_2") (pintype "unspecified"))
      (node (ref "C44") (pin "2") (pinfunction "2_2") (pintype "unspecified"))
      (node (ref "C45") (pin "2") (pinfunction "2_2") (pintype "unspecified"))
      (node (ref "C46") (pin "2") (pinfunction "2_2") (pintype "unspecified"))
      (node (ref "C5") (pin "2") (pinfunction "2_2") (pintype "unspecified"))
      (node (ref "C6") (pin "2") (pinfunction "2_2") (pintype "unspecified"))
      (node (ref "C7") (pin "2") (pinfunction "2_2") (pintype "unspecified"))
      (node (ref "C8") (pin "2") (pinfunction "2_2") (pintype "unspecified"))
      (node (ref "C9") (pin "2") (pinfunction "2_2") (pintype "unspecified"))
      (node (ref "D1") (pin "2") (pinfunction "2_2") (pintype "unspecified"))
      (node (ref "J1") (pin "A1/B12") (pinfunction "A1/B12_A1/B12") (pintype "unspecified"))
      (node (ref "J1") (pin "A12/B1") (pinfunction "A12/B1_A12/B1") (pintype "unspecified"))
      (node (ref "J1") (pin "S1") (pinfunction "S1_S1") (pintype "unspecified"))
      (node (ref "J1") (pin "S2") (pinfunction "S2_S2") (pintype "unspecified"))
      (node (ref "J1") (pin "S3") (pinfunction "S3_S3") (pintype "unspecified"))
      (node (ref "J1") (pin "S4") (pinfunction "S4_S4") (pintype "unspecified"))
      (node (ref "J2") (pin "15") (pinfunction "15_15") (pintype "unspecified"))
      (node (ref "J2") (pin "18") (pinfunction "18_18") (pintype "unspecified"))
      (node (ref "J2") (pin "21") (pinfunction "21_21") (pintype "unspecified"))
      (node (ref "J2") (pin "24") (pinfunction "24_24") (pintype "unspecified"))
      (node (ref "J2") (pin "5") (pinfunction "5_5") (pintype "unspecified"))
      (node (ref "J2") (pin "6") (pinfunction "6_6") (pintype "unspecified"))
      (node (ref "J2") (pin "7") (pinfunction "7_7") (pintype "unspecified"))
      (node (ref "J2") (pin "MP") (pinfunction "MP_MP") (pintype "unspecified"))
      (node (ref "J3") (pin "2") (pinfunction "2_2") (pintype "unspecified"))
      (node (ref "J3") (pin "MP") (pinfunction "MP_MP") (pintype "unspecified"))
      (node (ref "J4") (pin "MP") (pinfunction "MP_MP") (pintype "unspecified"))
      (node (ref "J5") (pin "4") (pinfunction "4_4") (pintype "unspecified"))
      (node (ref "J5") (pin "MP") (pinfunction "MP_MP") (pintype "unspecified"))
      (node (ref "J6") (pin "2") (pinfunction "2_2") (pintype "unspecified"))
      (node (ref "LED1") (pin "2") (pinfunction "GND_2") (pintype "unspecified"))
      (node (ref "LED2") (pin "2") (pinfunction "GND_2") (pintype "unspecified"))
      (node (ref "LED3") (pin "2") (pinfunction "GND_2") (pintype "unspecified"))
      (node (ref "LED4") (pin "2") (pinfunction "GND_2") (pintype "unspecified"))
      (node (ref "R12") (pin "2") (pinfunction "2_2") (pintype "unspecified"))
      (node (ref "R28") (pin "2") (pinfunction "2_2") (pintype "unspecified"))
      (node (ref "R30") (pin "2") (pinfunction "2_2") (pintype "unspecified"))
      (node (ref "R33") (pin "2") (pinfunction "2_2") (pintype "unspecified"))
      (node (ref "R4") (pin "2") (pinfunction "2_2") (pintype "unspecified"))
      (node (ref "R8") (pin "2") (pinfunction "2_2") (pintype "unspecified"))
      (node (ref "R9") (pin "2") (pinfunction "2_2") (pintype "unspecified"))
      (node (ref "SW1") (pin "2") (pinfunction "2_2") (pintype "unspecified"))
      (node (ref "SW2") (pin "2") (pinfunction "2_2") (pintype "unspecified"))
      (node (ref "SW3") (pin "2") (pinfunction "2_2") (pintype "unspecified"))
      (node (ref "TP1") (pin "1") (pinfunction "1_1") (pintype "unspecified"))
      (node (ref "U1") (pin "33") (pinfunction "EP/GND_33") (pintype "unspecified"))
      (node (ref "U2") (pin "4") (pinfunction "GND_4") (pintype "unspecified"))
      (node (ref "U3") (pin "7") (pinfunction "GND_7") (pintype "unspecified"))
      (node (ref "U4") (pin "2") (pinfunction "GND_2") (pintype "unspecified"))
      (node (ref "U5") (pin "4") (pinfunction "GND_4") (pintype "unspecified"))
      (node (ref "U6") (pin "2") (pinfunction "GND_2") (pintype "unspecified"))
      (node (ref "Y1") (pin "2") (pinfunction "2_2") (pintype "unspecified"))
      (node (ref "Y1") (pin "4") (pinfunction "4_4") (pintype "unspecified"))
    )
    (net (code "10") (name "LCD_CLK_3V0") (class "Default")
      (node (ref "J2") (pin "16") (pinfunction "16_16") (pintype "unspecified"))
      (node (ref "U5") (pin "2") (pinfunction "3Y_2") (pintype "unspecified"))
    )
    (net (code "11") (name "LCD_DC") (class "Default")
      (node (ref "U1") (pin "16") (pinfunction "GPIO10_16") (pintype "unspecified"))
      (node (ref "U5") (pin "3") (pinfunction "2A_3") (pintype "unspecified"))
    )
    (net (code "12") (name "LCD_DC_3V0") (class "Default")
      (node (ref "J2") (pin "17") (pinfunction "17_17") (pintype "unspecified"))
      (node (ref "U5") (pin "5") (pinfunction "2Y_5") (pintype "unspecified"))
    )
    (net (code "13") (name "LCD_LEDA") (class "Default")
      (node (ref "J2") (pin "8") (pinfunction "8_8") (pintype "unspecified"))
      (node (ref "R14") (pin "2") (pinfunction "2_2") (pintype "unspecified"))
    )
    (net (code "14") (name "LCD_MOSI") (class "Default")
      (node (ref "U1") (pin "9") (pinfunction "GPIO4_9") (pintype "unspecified"))
      (node (ref "U5") (pin "1") (pinfunction "1A_1") (pintype "unspecified"))
    )
    (net (code "15") (name "LCD_MOSI_3V0") (class "Default")
      (node (ref "J2") (pin "19") (pinfunction "19_19") (pintype "unspecified"))
      (node (ref "U5") (pin "7") (pinfunction "1Y_7") (pintype "unspecified"))
    )
    (net (code "16") (name "LCD_RESET_N") (class "Default")
      (node (ref "C23") (pin "1") (pinfunction "1_1") (pintype "unspecified"))
      (node (ref "D2") (pin "2") (pinfunction "2_2") (pintype "unspecified"))
      (node (ref "J2") (pin "20") (pinfunction "20_20") (pintype "unspecified"))
      (node (ref "R13") (pin "2") (pinfunction "2_2") (pintype "unspecified"))
    )
    (net (code "17") (name "LCD_SCLK") (class "Default")
      (node (ref "R12") (pin "1") (pinfunction "1_1") (pintype "unspecified"))
      (node (ref "U1") (pin "10") (pinfunction "GPIO5_10") (pintype "unspecified"))
      (node (ref "U5") (pin "6") (pinfunction "3A_6") (pintype "unspecified"))
    )
    (net (code "18") (name "MIC_3V4") (class "Default")
      (node (ref "C35") (pin "1") (pinfunction "1_1") (pintype "unspecified"))
      (node (ref "R23") (pin "2") (pinfunction "2_2") (pintype "unspecified"))
      (node (ref "R24") (pin "1") (pinfunction "1_1") (pintype "unspecified"))
    )
    (net (code "19") (name "MIC_AC") (class "Default")
      (node (ref "C38") (pin "2") (pinfunction "2_2") (pintype "unspecified"))
      (node (ref "R25") (pin "1") (pinfunction "1_1") (pintype "unspecified"))
    )
    (net (code "20") (name "MIC_ADC") (class "Default")
      (node (ref "C41") (pin "2") (pinfunction "2_2") (pintype "unspecified"))
      (node (ref "R29") (pin "2") (pinfunction "2_2") (pintype "unspecified"))
      (node (ref "R30") (pin "1") (pinfunction "1_1") (pintype "unspecified"))
      (node (ref "U1") (pin "6") (pinfunction "GPIO2/ADC1_CH2_6") (pintype "unspecified"))
    )
    (net (code "21") (name "MIC_BIAS") (class "Default")
      (node (ref "C40") (pin "1") (pinfunction "1_1") (pintype "unspecified"))
      (node (ref "R27") (pin "2") (pinfunction "2_2") (pintype "unspecified"))
      (node (ref "R28") (pin "1") (pinfunction "1_1") (pintype "unspecified"))
      (node (ref "U4") (pin "1") (pinfunction "IN+_1") (pintype "unspecified"))
    )
    (net (code "22") (name "MIC_INV") (class "Default")
      (node (ref "C39") (pin "1") (pinfunction "1_1") (pintype "unspecified"))
      (node (ref "R25") (pin "2") (pinfunction "2_2") (pintype "unspecified"))
      (node (ref "R26") (pin "1") (pinfunction "1_1") (pintype "unspecified"))
      (node (ref "U4") (pin "3") (pinfunction "IN-_3") (pintype "unspecified"))
    )
    (net (code "23") (name "MIC_OUT") (class "Default")
      (node (ref "C39") (pin "2") (pinfunction "2_2") (pintype "unspecified"))
      (node (ref "C41") (pin "1") (pinfunction "1_1") (pintype "unspecified"))
      (node (ref "R26") (pin "2") (pinfunction "2_2") (pintype "unspecified"))
      (node (ref "U4") (pin "4") (pinfunction "OUT_4") (pintype "unspecified"))
    )
    (net (code "24") (name "MIC_P") (class "Default")
      (node (ref "C37") (pin "1") (pinfunction "1_1") (pintype "unspecified"))
      (node (ref "C38") (pin "1") (pinfunction "1_1") (pintype "unspecified"))
      (node (ref "J3") (pin "1") (pinfunction "1_1") (pintype "unspecified"))
      (node (ref "R24") (pin "2") (pinfunction "2_2") (pintype "unspecified"))
    )
    (net (code "25") (name "PA_AC_N") (class "Default")
      (node (ref "C31") (pin "2") (pinfunction "2_2") (pintype "unspecified"))
      (node (ref "R22") (pin "1") (pinfunction "1_1") (pintype "unspecified"))
    )
    (net (code "26") (name "PA_AC_P") (class "Default")
      (node (ref "C30") (pin "2") (pinfunction "2_2") (pintype "unspecified"))
      (node (ref "R21") (pin "1") (pinfunction "1_1") (pintype "unspecified"))
    )
    (net (code "27") (name "PA_BYPASS") (class "Default")
      (node (ref "C32") (pin "1") (pinfunction "1_1") (pintype "unspecified"))
      (node (ref "U3") (pin "2") (pinfunction "BYPASS_2") (pintype "unspecified"))
    )
    (net (code "28") (name "PA_EN") (class "Default")
      (node (ref "R4") (pin "1") (pinfunction "1_1") (pintype "unspecified"))
      (node (ref "U1") (pin "8") (pinfunction "GPIO3_8") (pintype "unspecified"))
      (node (ref "U3") (pin "1") (pinfunction "CTRL_1") (pintype "unspecified"))
    )
    (net (code "29") (name "PA_INN") (class "Default")
      (node (ref "R22") (pin "2") (pinfunction "2_2") (pintype "unspecified"))
      (node (ref "U3") (pin "4") (pinfunction "INN_4") (pintype "unspecified"))
    )
    (net (code "30") (name "PA_INP") (class "Default")
      (node (ref "R21") (pin "2") (pinfunction "2_2") (pintype "unspecified"))
      (node (ref "U3") (pin "3") (pinfunction "INP_3") (pintype "unspecified"))
    )
    (net (code "31") (name "PDM_N") (class "Default")
      (node (ref "R18") (pin "1") (pinfunction "1_1") (pintype "unspecified"))
      (node (ref "U1") (pin "13") (pinfunction "GPIO7_13") (pintype "unspecified"))
    )
    (net (code "32") (name "PDM_N_F1") (class "Default")
      (node (ref "C27") (pin "1") (pinfunction "1_1") (pintype "unspecified"))
      (node (ref "R18") (pin "2") (pinfunction "2_2") (pintype "unspecified"))
      (node (ref "R19") (pin "1") (pinfunction "1_1") (pintype "unspecified"))
    )
    (net (code "33") (name "PDM_N_F2") (class "Default")
      (node (ref "C28") (pin "1") (pinfunction "1_1") (pintype "unspecified"))
      (node (ref "R19") (pin "2") (pinfunction "2_2") (pintype "unspecified"))
      (node (ref "R20") (pin "1") (pinfunction "1_1") (pintype "unspecified"))
    )
    (net (code "34") (name "PDM_N_F3") (class "Default")
      (node (ref "C29") (pin "1") (pinfunction "1_1") (pintype "unspecified"))
      (node (ref "C31") (pin "1") (pinfunction "1_1") (pintype "unspecified"))
      (node (ref "R20") (pin "2") (pinfunction "2_2") (pintype "unspecified"))
    )
    (net (code "35") (name "PDM_P") (class "Default")
      (node (ref "R15") (pin "1") (pinfunction "1_1") (pintype "unspecified"))
      (node (ref "U1") (pin "12") (pinfunction "GPIO6_12") (pintype "unspecified"))
    )
    (net (code "36") (name "PDM_P_F1") (class "Default")
      (node (ref "C24") (pin "1") (pinfunction "1_1") (pintype "unspecified"))
      (node (ref "R15") (pin "2") (pinfunction "2_2") (pintype "unspecified"))
      (node (ref "R16") (pin "1") (pinfunction "1_1") (pintype "unspecified"))
    )
    (net (code "37") (name "PDM_P_F2") (class "Default")
      (node (ref "C25") (pin "1") (pinfunction "1_1") (pintype "unspecified"))
      (node (ref "R16") (pin "2") (pinfunction "2_2") (pintype "unspecified"))
      (node (ref "R17") (pin "1") (pinfunction "1_1") (pintype "unspecified"))
    )
    (net (code "38") (name "PDM_P_F3") (class "Default")
      (node (ref "C26") (pin "1") (pinfunction "1_1") (pintype "unspecified"))
      (node (ref "C30") (pin "1") (pinfunction "1_1") (pintype "unspecified"))
      (node (ref "R17") (pin "2") (pinfunction "2_2") (pintype "unspecified"))
    )
    (net (code "39") (name "RF_3V4") (class "Default")
      (node (ref "C8") (pin "1") (pinfunction "1_1") (pintype "unspecified"))
      (node (ref "L1") (pin "2") (pinfunction "2_2") (pintype "unspecified"))
      (node (ref "U1") (pin "2") (pinfunction "VDD3P3_2") (pintype "unspecified"))
      (node (ref "U1") (pin "3") (pinfunction "VDD3P3_3") (pintype "unspecified"))
    )
    (net (code "40") (name "RF_50") (class "Default")
      (node (ref "C13") (pin "1") (pinfunction "1_1") (pintype "unspecified"))
      (node (ref "J6") (pin "1") (pinfunction "1_1") (pintype "unspecified"))
      (node (ref "R7") (pin "2") (pinfunction "2_2") (pintype "unspecified"))
    )
    (net (code "41") (name "RF_CHIP") (class "Default")
      (node (ref "C12") (pin "1") (pinfunction "1_1") (pintype "unspecified"))
      (node (ref "R7") (pin "1") (pinfunction "1_1") (pintype "unspecified"))
      (node (ref "U1") (pin "1") (pinfunction "LNA_IN_1") (pintype "unspecified"))
    )
    (net (code "42") (name "RGB_3V4") (class "Default")
      (node (ref "R3") (pin "2") (pinfunction "2_2") (pintype "unspecified"))
      (node (ref "R31") (pin "1") (pinfunction "1_1") (pintype "unspecified"))
      (node (ref "U1") (pin "14") (pinfunction "GPIO8/STRAP_14") (pintype "unspecified"))
    )
    (net (code "43") (name "RGB_D1") (class "Default")
      (node (ref "LED1") (pin "3") (pinfunction "DI_3") (pintype "unspecified"))
      (node (ref "R31") (pin "2") (pinfunction "2_2") (pintype "unspecified"))
    )
    (net (code "44") (name "RGB_D2") (class "Default")
      (node (ref "LED1") (pin "1") (pinfunction "DO_1") (pintype "unspecified"))
      (node (ref "LED2") (pin "3") (pinfunction "DI_3") (pintype "unspecified"))
    )
    (net (code "45") (name "RGB_D3") (class "Default")
      (node (ref "LED2") (pin "1") (pinfunction "DO_1") (pintype "unspecified"))
      (node (ref "LED3") (pin "3") (pinfunction "DI_3") (pintype "unspecified"))
    )
    (net (code "46") (name "RGB_D4") (class "Default")
      (node (ref "LED3") (pin "1") (pinfunction "DO_1") (pintype "unspecified"))
      (node (ref "LED4") (pin "3") (pinfunction "DI_3") (pintype "unspecified"))
    )
    (net (code "47") (name "SPK_N") (class "Default")
      (node (ref "J4") (pin "2") (pinfunction "2_2") (pintype "unspecified"))
      (node (ref "U3") (pin "5") (pinfunction "VON_5") (pintype "unspecified"))
    )
    (net (code "48") (name "SPK_P") (class "Default")
      (node (ref "J4") (pin "1") (pinfunction "1_1") (pintype "unspecified"))
      (node (ref "U3") (pin "8") (pinfunction "VOP_8") (pintype "unspecified"))
    )
    (net (code "49") (name "SW_BUCK") (class "Default")
      (node (ref "C16") (pin "2") (pinfunction "2_2") (pintype "unspecified"))
      (node (ref "L3") (pin "1") (pinfunction "1_1") (pintype "unspecified"))
      (node (ref "U2") (pin "5") (pinfunction "SW_5") (pintype "unspecified"))
    )
    (net (code "50") (name "UART_RX") (class "Default")
      (node (ref "TP5") (pin "1") (pinfunction "1_1") (pintype "unspecified"))
      (node (ref "U1") (pin "27") (pinfunction "GPIO20/RX_27") (pintype "unspecified"))
    )
    (net (code "51") (name "UART_TX") (class "Default")
      (node (ref "TP4") (pin "1") (pinfunction "1_1") (pintype "unspecified"))
      (node (ref "U1") (pin "28") (pinfunction "GPIO21/TX_28") (pintype "unspecified"))
    )
    (net (code "52") (name "USB_DM") (class "Default")
      (node (ref "D1") (pin "1") (pinfunction "1_1") (pintype "unspecified"))
      (node (ref "D1") (pin "6") (pinfunction "6_6") (pintype "unspecified"))
      (node (ref "J1") (pin "A7") (pinfunction "A7_A7") (pintype "unspecified"))
      (node (ref "J1") (pin "B7") (pinfunction "B7_B7") (pintype "unspecified"))
      (node (ref "R10") (pin "1") (pinfunction "1_1") (pintype "unspecified"))
    )
    (net (code "53") (name "USB_DM_MCU") (class "Default")
      (node (ref "R10") (pin "2") (pinfunction "2_2") (pintype "unspecified"))
      (node (ref "U1") (pin "25") (pinfunction "GPIO18/USB_D-_25") (pintype "unspecified"))
    )
    (net (code "54") (name "USB_DP") (class "Default")
      (node (ref "D1") (pin "3") (pinfunction "3_3") (pintype "unspecified"))
      (node (ref "D1") (pin "4") (pinfunction "4_4") (pintype "unspecified"))
      (node (ref "J1") (pin "A6") (pinfunction "A6_A6") (pintype "unspecified"))
      (node (ref "J1") (pin "B6") (pinfunction "B6_B6") (pintype "unspecified"))
      (node (ref "R11") (pin "1") (pinfunction "1_1") (pintype "unspecified"))
    )
    (net (code "55") (name "USB_DP_MCU") (class "Default")
      (node (ref "R11") (pin "2") (pinfunction "2_2") (pintype "unspecified"))
      (node (ref "U1") (pin "26") (pinfunction "GPIO19/USB_D+_26") (pintype "unspecified"))
    )
    (net (code "56") (name "VBUS") (class "Default")
      (node (ref "C14") (pin "1") (pinfunction "1_1") (pintype "unspecified"))
      (node (ref "C15") (pin "1") (pinfunction "1_1") (pintype "unspecified"))
      (node (ref "D1") (pin "5") (pinfunction "5_5") (pintype "unspecified"))
      (node (ref "J1") (pin "A4/B9") (pinfunction "A4/B9_A4/B9") (pintype "unspecified"))
      (node (ref "J1") (pin "A9/B4") (pinfunction "A9/B4_A9/B4") (pintype "unspecified"))
      (node (ref "J5") (pin "3") (pinfunction "3_3") (pintype "unspecified"))
      (node (ref "R14") (pin "1") (pinfunction "1_1") (pintype "unspecified"))
      (node (ref "TP3") (pin "1") (pinfunction "1_1") (pintype "unspecified"))
      (node (ref "U2") (pin "2") (pinfunction "EN_2") (pintype "unspecified"))
      (node (ref "U2") (pin "3") (pinfunction "VIN_3") (pintype "unspecified"))
    )
    (net (code "57") (name "VDD_SPI") (class "Default")
      (node (ref "C3") (pin "1") (pinfunction "1_1") (pintype "unspecified"))
      (node (ref "U1") (pin "18") (pinfunction "VDD_SPI_18") (pintype "unspecified"))
    )
    (net (code "58") (name "WAKE_AUDIO") (class "Default")
      (node (ref "J5") (pin "2") (pinfunction "2_2") (pintype "unspecified"))
      (node (ref "R6") (pin "2") (pinfunction "2_2") (pintype "unspecified"))
      (node (ref "U1") (pin "5") (pinfunction "GPIO1_5") (pintype "unspecified"))
    )
    (net (code "59") (name "WAKE_MOVE") (class "Default")
      (node (ref "J5") (pin "1") (pinfunction "1_1") (pintype "unspecified"))
      (node (ref "R5") (pin "2") (pinfunction "2_2") (pintype "unspecified"))
      (node (ref "SW3") (pin "1") (pinfunction "1_1") (pintype "unspecified"))
      (node (ref "U1") (pin "4") (pinfunction "GPIO0_4") (pintype "unspecified"))
    )
    (net (code "60") (name "XTAL_LOAD") (class "Default")
      (node (ref "C9") (pin "1") (pinfunction "1_1") (pintype "unspecified"))
      (node (ref "L2") (pin "2") (pinfunction "2_2") (pintype "unspecified"))
      (node (ref "Y1") (pin "1") (pinfunction "1_1") (pintype "unspecified"))
    )
    (net (code "61") (name "XTAL_N") (class "Default")
      (node (ref "C10") (pin "1") (pinfunction "1_1") (pintype "unspecified"))
      (node (ref "U1") (pin "29") (pinfunction "XTAL_N_29") (pintype "unspecified"))
      (node (ref "Y1") (pin "3") (pinfunction "3_3") (pintype "unspecified"))
    )
    (net (code "62") (name "XTAL_P") (class "Default")
      (node (ref "L2") (pin "1") (pinfunction "1_1") (pintype "unspecified"))
      (node (ref "U1") (pin "30") (pinfunction "XTAL_P_30") (pintype "unspecified"))
    )
    (net (code "63") (name "unconnected-(J1-PadA8)") (class "Default")
      (node (ref "J1") (pin "A8") (pinfunction "A8_A8") (pintype "unspecified+no_connect"))
    )
    (net (code "64") (name "unconnected-(J1-PadB8)") (class "Default")
      (node (ref "J1") (pin "B8") (pinfunction "B8_B8") (pintype "unspecified+no_connect"))
    )
    (net (code "65") (name "unconnected-(J2-Pad1)") (class "Default")
      (node (ref "J2") (pin "1") (pinfunction "1_1") (pintype "unspecified+no_connect"))
    )
    (net (code "66") (name "unconnected-(J2-Pad2)") (class "Default")
      (node (ref "J2") (pin "2") (pinfunction "2_2") (pintype "unspecified+no_connect"))
    )
    (net (code "67") (name "unconnected-(J2-Pad3)") (class "Default")
      (node (ref "J2") (pin "3") (pinfunction "3_3") (pintype "unspecified+no_connect"))
    )
    (net (code "68") (name "unconnected-(J2-Pad4)") (class "Default")
      (node (ref "J2") (pin "4") (pinfunction "4_4") (pintype "unspecified+no_connect"))
    )
    (net (code "69") (name "unconnected-(J2-Pad9)") (class "Default")
      (node (ref "J2") (pin "9") (pinfunction "9_9") (pintype "unspecified+no_connect"))
    )
    (net (code "70") (name "unconnected-(J2-Pad10)") (class "Default")
      (node (ref "J2") (pin "10") (pinfunction "10_10") (pintype "unspecified+no_connect"))
    )
    (net (code "71") (name "unconnected-(J2-Pad11)") (class "Default")
      (node (ref "J2") (pin "11") (pinfunction "11_11") (pintype "unspecified+no_connect"))
    )
    (net (code "72") (name "unconnected-(J2-Pad12)") (class "Default")
      (node (ref "J2") (pin "12") (pinfunction "12_12") (pintype "unspecified+no_connect"))
    )
    (net (code "73") (name "unconnected-(J2-Pad13)") (class "Default")
      (node (ref "J2") (pin "13") (pinfunction "13_13") (pintype "unspecified+no_connect"))
    )
    (net (code "74") (name "unconnected-(LED4-DO-Pad1)") (class "Default")
      (node (ref "LED4") (pin "1") (pinfunction "DO_1") (pintype "unspecified+no_connect"))
    )
    (net (code "75") (name "unconnected-(U1-NC-Pad19)") (class "Default")
      (node (ref "U1") (pin "19") (pinfunction "NC_19") (pintype "unspecified+no_connect"))
    )
    (net (code "76") (name "unconnected-(U1-NC-Pad20)") (class "Default")
      (node (ref "U1") (pin "20") (pinfunction "NC_20") (pintype "unspecified+no_connect"))
    )
    (net (code "77") (name "unconnected-(U1-NC-Pad21)") (class "Default")
      (node (ref "U1") (pin "21") (pinfunction "NC_21") (pintype "unspecified+no_connect"))
    )
    (net (code "78") (name "unconnected-(U1-NC-Pad22)") (class "Default")
      (node (ref "U1") (pin "22") (pinfunction "NC_22") (pintype "unspecified+no_connect"))
    )
    (net (code "79") (name "unconnected-(U1-NC-Pad23)") (class "Default")
      (node (ref "U1") (pin "23") (pinfunction "NC_23") (pintype "unspecified+no_connect"))
    )
    (net (code "80") (name "unconnected-(U1-NC-Pad24)") (class "Default")
      (node (ref "U1") (pin "24") (pinfunction "NC_24") (pintype "unspecified+no_connect"))
    )
    (net (code "81") (name "unconnected-(U6-NC-Pad4)") (class "Default")
      (node (ref "U6") (pin "4") (pinfunction "NC_4") (pintype "unspecified+no_connect"))
    )
  )
)
